# GS_01_Core.net
KiCad netlist of a schematic drawn in Altium Designer
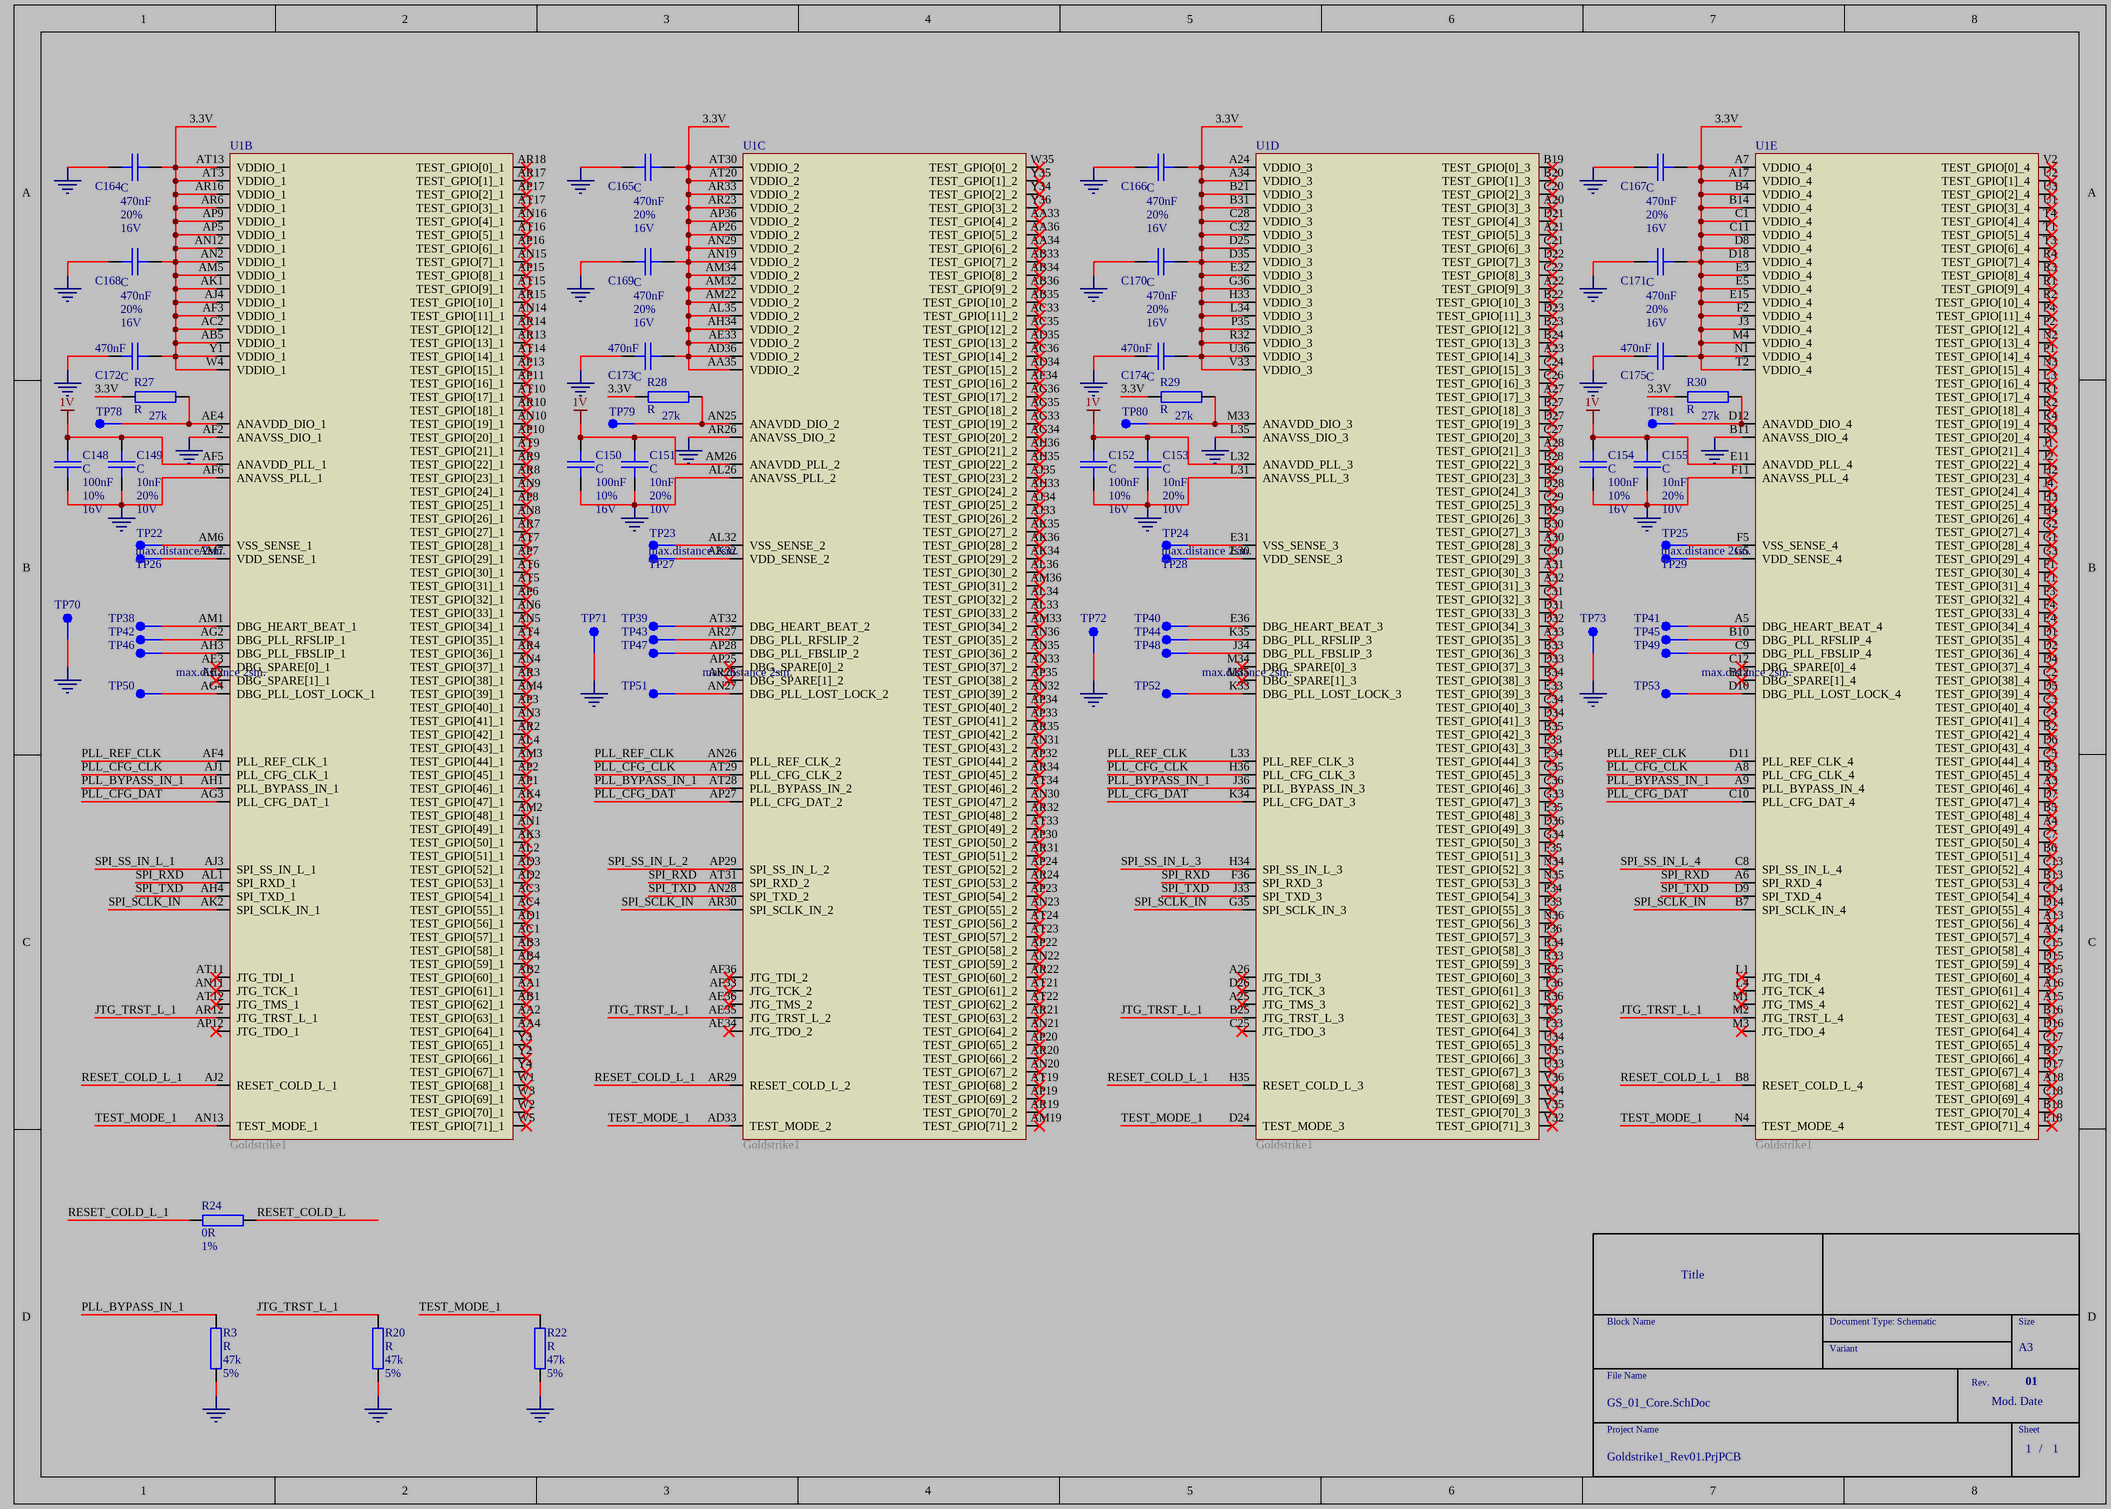
[diagram p0: GS_01_Core.SchDoc]

(export (version "E")
  (design (tool "Eeschema 10.0.6"))
  (components
    (comp (ref "C148")
      (value "C")
      (footprint "SMD_0603_CAPC1608X95N")
      (fields
        (field (name "DB_PART_NUMBER") "CAP000047357")
        (field (name "DB_VALUE") "100nF")
        (field (name "DB_TOLERANCE") "10%")
        (field (name "DB_VOLTAGE") "16V")
      )
      (libsource (lib "Database_Libs1") (part "C"))
    )
    (comp (ref "C149")
      (value "C")
      (footprint "SMD_0603_CAPC1608X95N")
      (fields
        (field (name "DB_PART_NUMBER") "CAP000038821")
        (field (name "DB_VALUE") "10nF")
        (field (name "DB_TOLERANCE") "20%")
        (field (name "DB_VOLTAGE") "10V")
      )
      (libsource (lib "Database_Libs1") (part "C"))
    )
    (comp (ref "C150")
      (value "C")
      (footprint "SMD_0603_CAPC1608X95N")
      (fields
        (field (name "DB_PART_NUMBER") "CAP000047357")
        (field (name "DB_VALUE") "100nF")
        (field (name "DB_TOLERANCE") "10%")
        (field (name "DB_VOLTAGE") "16V")
      )
      (libsource (lib "Database_Libs1") (part "C"))
    )
    (comp (ref "C151")
      (value "C")
      (footprint "SMD_0603_CAPC1608X95N")
      (fields
        (field (name "DB_PART_NUMBER") "CAP000038821")
        (field (name "DB_VALUE") "10nF")
        (field (name "DB_TOLERANCE") "20%")
        (field (name "DB_VOLTAGE") "10V")
      )
      (libsource (lib "Database_Libs1") (part "C"))
    )
    (comp (ref "C152")
      (value "C")
      (footprint "SMD_0603_CAPC1608X95N")
      (fields
        (field (name "DB_PART_NUMBER") "CAP000047357")
        (field (name "DB_VALUE") "100nF")
        (field (name "DB_TOLERANCE") "10%")
        (field (name "DB_VOLTAGE") "16V")
      )
      (libsource (lib "Database_Libs1") (part "C"))
    )
    (comp (ref "C153")
      (value "C")
      (footprint "SMD_0603_CAPC1608X95N")
      (fields
        (field (name "DB_PART_NUMBER") "CAP000038821")
        (field (name "DB_VALUE") "10nF")
        (field (name "DB_TOLERANCE") "20%")
        (field (name "DB_VOLTAGE") "10V")
      )
      (libsource (lib "Database_Libs1") (part "C"))
    )
    (comp (ref "C154")
      (value "C")
      (footprint "SMD_0603_CAPC1608X95N")
      (fields
        (field (name "DB_PART_NUMBER") "CAP000047357")
        (field (name "DB_VALUE") "100nF")
        (field (name "DB_TOLERANCE") "10%")
        (field (name "DB_VOLTAGE") "16V")
      )
      (libsource (lib "Database_Libs1") (part "C"))
    )
    (comp (ref "C155")
      (value "C")
      (footprint "SMD_0603_CAPC1608X95N")
      (fields
        (field (name "DB_PART_NUMBER") "CAP000038821")
        (field (name "DB_VALUE") "10nF")
        (field (name "DB_TOLERANCE") "20%")
        (field (name "DB_VOLTAGE") "10V")
      )
      (libsource (lib "Database_Libs1") (part "C"))
    )
    (comp (ref "C164")
      (value "C")
      (footprint "SMD_0603_CAPC1608X95N")
      (fields
        (field (name "DB_PART_NUMBER") "CAP000023179")
        (field (name "DB_VALUE") "470nF")
        (field (name "DB_TOLERANCE") "20%")
        (field (name "DB_VOLTAGE") "16V")
        (field (name "DB_MANUFACTURER_PART") "KEMET    C0603F474M4RAC")
      )
      (libsource (lib "Database_Libs1") (part "C"))
    )
    (comp (ref "C165")
      (value "C")
      (footprint "SMD_0603_CAPC1608X95N")
      (fields
        (field (name "DB_PART_NUMBER") "CAP000023179")
        (field (name "DB_VALUE") "470nF")
        (field (name "DB_TOLERANCE") "20%")
        (field (name "DB_VOLTAGE") "16V")
        (field (name "DB_MANUFACTURER_PART") "KEMET    C0603F474M4RAC")
      )
      (libsource (lib "Database_Libs1") (part "C"))
    )
    (comp (ref "C166")
      (value "C")
      (footprint "SMD_0603_CAPC1608X95N")
      (fields
        (field (name "DB_PART_NUMBER") "CAP000023179")
        (field (name "DB_VALUE") "470nF")
        (field (name "DB_TOLERANCE") "20%")
        (field (name "DB_VOLTAGE") "16V")
        (field (name "DB_MANUFACTURER_PART") "KEMET    C0603F474M4RAC")
      )
      (libsource (lib "Database_Libs1") (part "C"))
    )
    (comp (ref "C167")
      (value "C")
      (footprint "SMD_0603_CAPC1608X95N")
      (fields
        (field (name "DB_PART_NUMBER") "CAP000023179")
        (field (name "DB_VALUE") "470nF")
        (field (name "DB_TOLERANCE") "20%")
        (field (name "DB_VOLTAGE") "16V")
        (field (name "DB_MANUFACTURER_PART") "KEMET    C0603F474M4RAC")
      )
      (libsource (lib "Database_Libs1") (part "C"))
    )
    (comp (ref "C168")
      (value "C")
      (footprint "SMD_0603_CAPC1608X95N")
      (fields
        (field (name "DB_PART_NUMBER") "CAP000023179")
        (field (name "DB_VALUE") "470nF")
        (field (name "DB_TOLERANCE") "20%")
        (field (name "DB_VOLTAGE") "16V")
        (field (name "DB_MANUFACTURER_PART") "KEMET    C0603F474M4RAC")
      )
      (libsource (lib "Database_Libs1") (part "C"))
    )
    (comp (ref "C169")
      (value "C")
      (footprint "SMD_0603_CAPC1608X95N")
      (fields
        (field (name "DB_PART_NUMBER") "CAP000023179")
        (field (name "DB_VALUE") "470nF")
        (field (name "DB_TOLERANCE") "20%")
        (field (name "DB_VOLTAGE") "16V")
        (field (name "DB_MANUFACTURER_PART") "KEMET    C0603F474M4RAC")
      )
      (libsource (lib "Database_Libs1") (part "C"))
    )
    (comp (ref "C170")
      (value "C")
      (footprint "SMD_0603_CAPC1608X95N")
      (fields
        (field (name "DB_PART_NUMBER") "CAP000023179")
        (field (name "DB_VALUE") "470nF")
        (field (name "DB_TOLERANCE") "20%")
        (field (name "DB_VOLTAGE") "16V")
        (field (name "DB_MANUFACTURER_PART") "KEMET    C0603F474M4RAC")
      )
      (libsource (lib "Database_Libs1") (part "C"))
    )
    (comp (ref "C171")
      (value "C")
      (footprint "SMD_0603_CAPC1608X95N")
      (fields
        (field (name "DB_PART_NUMBER") "CAP000023179")
        (field (name "DB_VALUE") "470nF")
        (field (name "DB_TOLERANCE") "20%")
        (field (name "DB_VOLTAGE") "16V")
        (field (name "DB_MANUFACTURER_PART") "KEMET    C0603F474M4RAC")
      )
      (libsource (lib "Database_Libs1") (part "C"))
    )
    (comp (ref "C172")
      (value "C")
      (footprint "SMD_0603_CAPC1608X95N")
      (fields
        (field (name "DB_PART_NUMBER") "CAP000023179")
        (field (name "DB_VALUE") "470nF")
        (field (name "DB_MANUFACTURER_PART") "KEMET    C0603F474M4RAC")
      )
      (libsource (lib "Database_Libs1") (part "C"))
    )
    (comp (ref "C173")
      (value "C")
      (footprint "SMD_0603_CAPC1608X95N")
      (fields
        (field (name "DB_PART_NUMBER") "CAP000023179")
        (field (name "DB_VALUE") "470nF")
        (field (name "DB_MANUFACTURER_PART") "KEMET    C0603F474M4RAC")
      )
      (libsource (lib "Database_Libs1") (part "C"))
    )
    (comp (ref "C174")
      (value "C")
      (footprint "SMD_0603_CAPC1608X95N")
      (fields
        (field (name "DB_PART_NUMBER") "CAP000023179")
        (field (name "DB_VALUE") "470nF")
        (field (name "DB_MANUFACTURER_PART") "KEMET    C0603F474M4RAC")
      )
      (libsource (lib "Database_Libs1") (part "C"))
    )
    (comp (ref "C175")
      (value "C")
      (footprint "SMD_0603_CAPC1608X95N")
      (fields
        (field (name "DB_PART_NUMBER") "CAP000023179")
        (field (name "DB_VALUE") "470nF")
        (field (name "DB_MANUFACTURER_PART") "KEMET    C0603F474M4RAC")
      )
      (libsource (lib "Database_Libs1") (part "C"))
    )
    (comp (ref "R3")
      (value "R")
      (footprint "SMD_0603_RESC1608X55N")
      (fields
        (field (name "DB_PART_NUMBER") "RES000006462")
        (field (name "DB_VALUE") "47k")
        (field (name "DB_TOLERANCE") "5%")
        (field (name "DB_MANUFACTURER_PART") "YAGEO    RC0603JR-0747K")
      )
      (libsource (lib "Database_Libs1") (part "R"))
    )
    (comp (ref "R20")
      (value "R")
      (footprint "SMD_0603_RESC1608X55N")
      (fields
        (field (name "DB_PART_NUMBER") "RES000006462")
        (field (name "DB_VALUE") "47k")
        (field (name "DB_TOLERANCE") "5%")
        (field (name "DB_MANUFACTURER_PART") "YAGEO    RC0603JR-0747K")
      )
      (libsource (lib "Database_Libs1") (part "R"))
    )
    (comp (ref "R22")
      (value "R")
      (footprint "SMD_0603_RESC1608X55N")
      (fields
        (field (name "DB_PART_NUMBER") "RES000006462")
        (field (name "DB_VALUE") "47k")
        (field (name "DB_TOLERANCE") "5%")
        (field (name "DB_MANUFACTURER_PART") "YAGEO    RC0603JR-0747K")
      )
      (libsource (lib "Database_Libs1") (part "R"))
    )
    (comp (ref "R24")
      (value "R")
      (footprint "SMD_0603_RESC1608X55N")
      (fields
        (field (name "DB_PART_NUMBER") "RES000008926")
        (field (name "DB_VALUE") "0R")
        (field (name "DB_TOLERANCE") "1%")
        (field (name "DB_MANUFACTURER_PART") "YAGEO    AC0603FR-070RL")
        (field (name "DB_APPROVED_BY") "VSN")
      )
      (libsource (lib "Database_Libs1") (part "R"))
    )
    (comp (ref "R27")
      (value "R")
      (footprint "SMD_0603_RESC1608X55N")
      (fields
        (field (name "DB_PART_NUMBER") "RES000006456")
        (field (name "DB_VALUE") "27k")
        (field (name "DB_MANUFACTURER_PART") "YAGEO    RC0603JR-0727K")
      )
      (libsource (lib "Database_Libs1") (part "R"))
    )
    (comp (ref "R28")
      (value "R")
      (footprint "SMD_0603_RESC1608X55N")
      (fields
        (field (name "DB_PART_NUMBER") "RES000006456")
        (field (name "DB_VALUE") "27k")
        (field (name "DB_MANUFACTURER_PART") "YAGEO    RC0603JR-0727K")
      )
      (libsource (lib "Database_Libs1") (part "R"))
    )
    (comp (ref "R29")
      (value "R")
      (footprint "SMD_0603_RESC1608X55N")
      (fields
        (field (name "DB_PART_NUMBER") "RES000006456")
        (field (name "DB_VALUE") "27k")
        (field (name "DB_MANUFACTURER_PART") "YAGEO    RC0603JR-0727K")
      )
      (libsource (lib "Database_Libs1") (part "R"))
    )
    (comp (ref "R30")
      (value "R")
      (footprint "SMD_0603_RESC1608X55N")
      (fields
        (field (name "DB_PART_NUMBER") "RES000006456")
        (field (name "DB_VALUE") "27k")
        (field (name "DB_MANUFACTURER_PART") "YAGEO    RC0603JR-0727K")
      )
      (libsource (lib "Database_Libs1") (part "R"))
    )
    (comp (ref "TP22")
      (value "TEST_POINT_1")
      (footprint "SMD_TP_100-254")
      (fields (field (name "DB_PART_NUMBER") "TPO000000001"))
      (libsource (lib "Database_Libs1") (part "TEST_POINT_1"))
    )
    (comp (ref "TP23")
      (value "TEST_POINT_1")
      (footprint "SMD_TP_100-254")
      (fields (field (name "DB_PART_NUMBER") "TPO000000001"))
      (libsource (lib "Database_Libs1") (part "TEST_POINT_1"))
    )
    (comp (ref "TP24")
      (value "TEST_POINT_1")
      (footprint "SMD_TP_100-254")
      (fields (field (name "DB_PART_NUMBER") "TPO000000001"))
      (libsource (lib "Database_Libs1") (part "TEST_POINT_1"))
    )
    (comp (ref "TP25")
      (value "TEST_POINT_1")
      (footprint "SMD_TP_100-254")
      (fields (field (name "DB_PART_NUMBER") "TPO000000001"))
      (libsource (lib "Database_Libs1") (part "TEST_POINT_1"))
    )
    (comp (ref "TP26")
      (value "TEST_POINT_1")
      (footprint "SMD_TP_100-254")
      (fields (field (name "DB_PART_NUMBER") "TPO000000001"))
      (libsource (lib "Database_Libs1") (part "TEST_POINT_1"))
    )
    (comp (ref "TP27")
      (value "TEST_POINT_1")
      (footprint "SMD_TP_100-254")
      (fields (field (name "DB_PART_NUMBER") "TPO000000001"))
      (libsource (lib "Database_Libs1") (part "TEST_POINT_1"))
    )
    (comp (ref "TP28")
      (value "TEST_POINT_1")
      (footprint "SMD_TP_100-254")
      (fields (field (name "DB_PART_NUMBER") "TPO000000001"))
      (libsource (lib "Database_Libs1") (part "TEST_POINT_1"))
    )
    (comp (ref "TP29")
      (value "TEST_POINT_1")
      (footprint "SMD_TP_100-254")
      (fields (field (name "DB_PART_NUMBER") "TPO000000001"))
      (libsource (lib "Database_Libs1") (part "TEST_POINT_1"))
    )
    (comp (ref "TP38")
      (value "TEST_POINT_1")
      (footprint "SMD_TP_100-254")
      (fields (field (name "DB_PART_NUMBER") "TPO000000001"))
      (libsource (lib "Database_Libs1") (part "TEST_POINT_1"))
    )
    (comp (ref "TP39")
      (value "TEST_POINT_1")
      (footprint "SMD_TP_100-254")
      (fields (field (name "DB_PART_NUMBER") "TPO000000001"))
      (libsource (lib "Database_Libs1") (part "TEST_POINT_1"))
    )
    (comp (ref "TP40")
      (value "TEST_POINT_1")
      (footprint "SMD_TP_100-254")
      (fields (field (name "DB_PART_NUMBER") "TPO000000001"))
      (libsource (lib "Database_Libs1") (part "TEST_POINT_1"))
    )
    (comp (ref "TP41")
      (value "TEST_POINT_1")
      (footprint "SMD_TP_100-254")
      (fields (field (name "DB_PART_NUMBER") "TPO000000001"))
      (libsource (lib "Database_Libs1") (part "TEST_POINT_1"))
    )
    (comp (ref "TP42")
      (value "TEST_POINT_1")
      (footprint "SMD_TP_100-254")
      (fields (field (name "DB_PART_NUMBER") "TPO000000001"))
      (libsource (lib "Database_Libs1") (part "TEST_POINT_1"))
    )
    (comp (ref "TP43")
      (value "TEST_POINT_1")
      (footprint "SMD_TP_100-254")
      (fields (field (name "DB_PART_NUMBER") "TPO000000001"))
      (libsource (lib "Database_Libs1") (part "TEST_POINT_1"))
    )
    (comp (ref "TP44")
      (value "TEST_POINT_1")
      (footprint "SMD_TP_100-254")
      (fields (field (name "DB_PART_NUMBER") "TPO000000001"))
      (libsource (lib "Database_Libs1") (part "TEST_POINT_1"))
    )
    (comp (ref "TP45")
      (value "TEST_POINT_1")
      (footprint "SMD_TP_100-254")
      (fields (field (name "DB_PART_NUMBER") "TPO000000001"))
      (libsource (lib "Database_Libs1") (part "TEST_POINT_1"))
    )
    (comp (ref "TP46")
      (value "TEST_POINT_1")
      (footprint "SMD_TP_100-254")
      (fields (field (name "DB_PART_NUMBER") "TPO000000001"))
      (libsource (lib "Database_Libs1") (part "TEST_POINT_1"))
    )
    (comp (ref "TP47")
      (value "TEST_POINT_1")
      (footprint "SMD_TP_100-254")
      (fields (field (name "DB_PART_NUMBER") "TPO000000001"))
      (libsource (lib "Database_Libs1") (part "TEST_POINT_1"))
    )
    (comp (ref "TP48")
      (value "TEST_POINT_1")
      (footprint "SMD_TP_100-254")
      (fields (field (name "DB_PART_NUMBER") "TPO000000001"))
      (libsource (lib "Database_Libs1") (part "TEST_POINT_1"))
    )
    (comp (ref "TP49")
      (value "TEST_POINT_1")
      (footprint "SMD_TP_100-254")
      (fields (field (name "DB_PART_NUMBER") "TPO000000001"))
      (libsource (lib "Database_Libs1") (part "TEST_POINT_1"))
    )
    (comp (ref "TP50")
      (value "TEST_POINT_1")
      (footprint "SMD_TP_100-254")
      (fields (field (name "DB_PART_NUMBER") "TPO000000001"))
      (libsource (lib "Database_Libs1") (part "TEST_POINT_1"))
    )
    (comp (ref "TP51")
      (value "TEST_POINT_1")
      (footprint "SMD_TP_100-254")
      (fields (field (name "DB_PART_NUMBER") "TPO000000001"))
      (libsource (lib "Database_Libs1") (part "TEST_POINT_1"))
    )
    (comp (ref "TP52")
      (value "TEST_POINT_1")
      (footprint "SMD_TP_100-254")
      (fields (field (name "DB_PART_NUMBER") "TPO000000001"))
      (libsource (lib "Database_Libs1") (part "TEST_POINT_1"))
    )
    (comp (ref "TP53")
      (value "TEST_POINT_1")
      (footprint "SMD_TP_100-254")
      (fields (field (name "DB_PART_NUMBER") "TPO000000001"))
      (libsource (lib "Database_Libs1") (part "TEST_POINT_1"))
    )
    (comp (ref "TP70")
      (value "TEST_POINT_1")
      (footprint "SMD_TP_100-254")
      (fields (field (name "DB_PART_NUMBER") "TPO000000001"))
      (libsource (lib "Database_Libs1") (part "TEST_POINT_1"))
    )
    (comp (ref "TP71")
      (value "TEST_POINT_1")
      (footprint "SMD_TP_100-254")
      (fields (field (name "DB_PART_NUMBER") "TPO000000001"))
      (libsource (lib "Database_Libs1") (part "TEST_POINT_1"))
    )
    (comp (ref "TP72")
      (value "TEST_POINT_1")
      (footprint "SMD_TP_100-254")
      (fields (field (name "DB_PART_NUMBER") "TPO000000001"))
      (libsource (lib "Database_Libs1") (part "TEST_POINT_1"))
    )
    (comp (ref "TP73")
      (value "TEST_POINT_1")
      (footprint "SMD_TP_100-254")
      (fields (field (name "DB_PART_NUMBER") "TPO000000001"))
      (libsource (lib "Database_Libs1") (part "TEST_POINT_1"))
    )
    (comp (ref "TP78")
      (value "TEST_POINT_1")
      (footprint "SMD_TP_100-254")
      (fields (field (name "DB_PART_NUMBER") "TPO000000001"))
      (libsource (lib "Database_Libs1") (part "TEST_POINT_1"))
    )
    (comp (ref "TP79")
      (value "TEST_POINT_1")
      (footprint "SMD_TP_100-254")
      (fields (field (name "DB_PART_NUMBER") "TPO000000001"))
      (libsource (lib "Database_Libs1") (part "TEST_POINT_1"))
    )
    (comp (ref "TP80")
      (value "TEST_POINT_1")
      (footprint "SMD_TP_100-254")
      (fields (field (name "DB_PART_NUMBER") "TPO000000001"))
      (libsource (lib "Database_Libs1") (part "TEST_POINT_1"))
    )
    (comp (ref "TP81")
      (value "TEST_POINT_1")
      (footprint "SMD_TP_100-254")
      (fields (field (name "DB_PART_NUMBER") "TPO000000001"))
      (libsource (lib "Database_Libs1") (part "TEST_POINT_1"))
    )
    (comp (ref "U1") (value "Goldstrike1") (libsource (lib "Schlib1") (part "Goldstrike1")))
  )
  (nets
    (net (code "1") (name "/3.3V") (class "Default")
      (node (ref "C164") (pin "2") (pinfunction "2_2") (pintype "passive"))
      (node (ref "C165") (pin "2") (pinfunction "2_2") (pintype "passive"))
      (node (ref "C166") (pin "2") (pinfunction "2_2") (pintype "passive"))
      (node (ref "C167") (pin "2") (pinfunction "2_2") (pintype "passive"))
      (node (ref "C168") (pin "2") (pinfunction "2_2") (pintype "passive"))
      (node (ref "C169") (pin "2") (pinfunction "2_2") (pintype "passive"))
      (node (ref "C170") (pin "2") (pinfunction "2_2") (pintype "passive"))
      (node (ref "C171") (pin "2") (pinfunction "2_2") (pintype "passive"))
      (node (ref "C172") (pin "2") (pinfunction "2_2") (pintype "passive"))
      (node (ref "C173") (pin "2") (pinfunction "2_2") (pintype "passive"))
      (node (ref "C174") (pin "2") (pinfunction "2_2") (pintype "passive"))
      (node (ref "C175") (pin "2") (pinfunction "2_2") (pintype "passive"))
      (node (ref "R27") (pin "1") (pinfunction "1_1") (pintype "passive"))
      (node (ref "R28") (pin "1") (pinfunction "1_1") (pintype "passive"))
      (node (ref "R29") (pin "1") (pinfunction "1_1") (pintype "passive"))
      (node (ref "R30") (pin "1") (pinfunction "1_1") (pintype "passive"))
      (node (ref "U1") (pin "A17") (pinfunction "VDDIO_4_A17") (pintype "passive"))
      (node (ref "U1") (pin "A24") (pinfunction "VDDIO_3_A24") (pintype "passive"))
      (node (ref "U1") (pin "A34") (pinfunction "VDDIO_3_A34") (pintype "passive"))
      (node (ref "U1") (pin "A7") (pinfunction "VDDIO_4_A7") (pintype "passive"))
      (node (ref "U1") (pin "AA35") (pinfunction "VDDIO_2_AA35") (pintype "passive"))
      (node (ref "U1") (pin "AB5") (pinfunction "VDDIO_1_AB5") (pintype "passive"))
      (node (ref "U1") (pin "AC2") (pinfunction "VDDIO_1_AC2") (pintype "passive"))
      (node (ref "U1") (pin "AD36") (pinfunction "VDDIO_2_AD36") (pintype "passive"))
      (node (ref "U1") (pin "AE33") (pinfunction "VDDIO_2_AE33") (pintype "passive"))
      (node (ref "U1") (pin "AF3") (pinfunction "VDDIO_1_AF3") (pintype "passive"))
      (node (ref "U1") (pin "AH34") (pinfunction "VDDIO_2_AH34") (pintype "passive"))
      (node (ref "U1") (pin "AJ4") (pinfunction "VDDIO_1_AJ4") (pintype "passive"))
      (node (ref "U1") (pin "AK1") (pinfunction "VDDIO_1_AK1") (pintype "passive"))
      (node (ref "U1") (pin "AL35") (pinfunction "VDDIO_2_AL35") (pintype "passive"))
      (node (ref "U1") (pin "AM22") (pinfunction "VDDIO_2_AM22") (pintype "passive"))
      (node (ref "U1") (pin "AM32") (pinfunction "VDDIO_2_AM32") (pintype "passive"))
      (node (ref "U1") (pin "AM34") (pinfunction "VDDIO_2_AM34") (pintype "passive"))
      (node (ref "U1") (pin "AM5") (pinfunction "VDDIO_1_AM5") (pintype "passive"))
      (node (ref "U1") (pin "AN12") (pinfunction "VDDIO_1_AN12") (pintype "passive"))
      (node (ref "U1") (pin "AN19") (pinfunction "VDDIO_2_AN19") (pintype "passive"))
      (node (ref "U1") (pin "AN2") (pinfunction "VDDIO_1_AN2") (pintype "passive"))
      (node (ref "U1") (pin "AN29") (pinfunction "VDDIO_2_AN29") (pintype "passive"))
      (node (ref "U1") (pin "AP26") (pinfunction "VDDIO_2_AP26") (pintype "passive"))
      (node (ref "U1") (pin "AP36") (pinfunction "VDDIO_2_AP36") (pintype "passive"))
      (node (ref "U1") (pin "AP5") (pinfunction "VDDIO_1_AP5") (pintype "passive"))
      (node (ref "U1") (pin "AP9") (pinfunction "VDDIO_1_AP9") (pintype "passive"))
      (node (ref "U1") (pin "AR16") (pinfunction "VDDIO_1_AR16") (pintype "passive"))
      (node (ref "U1") (pin "AR23") (pinfunction "VDDIO_2_AR23") (pintype "passive"))
      (node (ref "U1") (pin "AR33") (pinfunction "VDDIO_2_AR33") (pintype "passive"))
      (node (ref "U1") (pin "AR6") (pinfunction "VDDIO_1_AR6") (pintype "passive"))
      (node (ref "U1") (pin "AT13") (pinfunction "VDDIO_1_AT13") (pintype "passive"))
      (node (ref "U1") (pin "AT20") (pinfunction "VDDIO_2_AT20") (pintype "passive"))
      (node (ref "U1") (pin "AT3") (pinfunction "VDDIO_1_AT3") (pintype "passive"))
      (node (ref "U1") (pin "AT30") (pinfunction "VDDIO_2_AT30") (pintype "passive"))
      (node (ref "U1") (pin "B14") (pinfunction "VDDIO_4_B14") (pintype "passive"))
      (node (ref "U1") (pin "B21") (pinfunction "VDDIO_3_B21") (pintype "passive"))
      (node (ref "U1") (pin "B31") (pinfunction "VDDIO_3_B31") (pintype "passive"))
      (node (ref "U1") (pin "B4") (pinfunction "VDDIO_4_B4") (pintype "passive"))
      (node (ref "U1") (pin "C1") (pinfunction "VDDIO_4_C1") (pintype "passive"))
      (node (ref "U1") (pin "C11") (pinfunction "VDDIO_4_C11") (pintype "passive"))
      (node (ref "U1") (pin "C28") (pinfunction "VDDIO_3_C28") (pintype "passive"))
      (node (ref "U1") (pin "C32") (pinfunction "VDDIO_3_C32") (pintype "passive"))
      (node (ref "U1") (pin "D18") (pinfunction "VDDIO_4_D18") (pintype "passive"))
      (node (ref "U1") (pin "D25") (pinfunction "VDDIO_3_D25") (pintype "passive"))
      (node (ref "U1") (pin "D35") (pinfunction "VDDIO_3_D35") (pintype "passive"))
      (node (ref "U1") (pin "D8") (pinfunction "VDDIO_4_D8") (pintype "passive"))
      (node (ref "U1") (pin "E15") (pinfunction "VDDIO_4_E15") (pintype "passive"))
      (node (ref "U1") (pin "E3") (pinfunction "VDDIO_4_E3") (pintype "passive"))
      (node (ref "U1") (pin "E32") (pinfunction "VDDIO_3_E32") (pintype "passive"))
      (node (ref "U1") (pin "E5") (pinfunction "VDDIO_4_E5") (pintype "passive"))
      (node (ref "U1") (pin "F2") (pinfunction "VDDIO_4_F2") (pintype "passive"))
      (node (ref "U1") (pin "G36") (pinfunction "VDDIO_3_G36") (pintype "passive"))
      (node (ref "U1") (pin "H33") (pinfunction "VDDIO_3_H33") (pintype "passive"))
      (node (ref "U1") (pin "J3") (pinfunction "VDDIO_4_J3") (pintype "passive"))
      (node (ref "U1") (pin "L34") (pinfunction "VDDIO_3_L34") (pintype "passive"))
      (node (ref "U1") (pin "M4") (pinfunction "VDDIO_4_M4") (pintype "passive"))
      (node (ref "U1") (pin "N1") (pinfunction "VDDIO_4_N1") (pintype "passive"))
      (node (ref "U1") (pin "P35") (pinfunction "VDDIO_3_P35") (pintype "passive"))
      (node (ref "U1") (pin "R32") (pinfunction "VDDIO_3_R32") (pintype "passive"))
      (node (ref "U1") (pin "T2") (pinfunction "VDDIO_4_T2") (pintype "passive"))
      (node (ref "U1") (pin "U36") (pinfunction "VDDIO_3_U36") (pintype "passive"))
      (node (ref "U1") (pin "V33") (pinfunction "VDDIO_3_V33") (pintype "passive"))
      (node (ref "U1") (pin "W4") (pinfunction "VDDIO_1_W4") (pintype "passive"))
      (node (ref "U1") (pin "Y1") (pinfunction "VDDIO_1_Y1") (pintype "passive"))
    )
    (net (code "2") (name "/JTG_TRST_L_1") (class "Default")
      (node (ref "R20") (pin "1") (pinfunction "1_1") (pintype "passive"))
      (node (ref "U1") (pin "AE35") (pinfunction "JTG_TRST_L_2_AE35") (pintype "passive"))
      (node (ref "U1") (pin "AR12") (pinfunction "JTG_TRST_L_1_AR12") (pintype "passive"))
      (node (ref "U1") (pin "B25") (pinfunction "JTG_TRST_L_3_B25") (pintype "passive"))
      (node (ref "U1") (pin "M2") (pinfunction "JTG_TRST_L_4_M2") (pintype "passive"))
    )
    (net (code "3") (name "/PLL_BYPASS_IN_1") (class "Default")
      (node (ref "R3") (pin "1") (pinfunction "1_1") (pintype "passive"))
      (node (ref "U1") (pin "A9") (pinfunction "PLL_BYPASS_IN_4_A9") (pintype "passive"))
      (node (ref "U1") (pin "AH1") (pinfunction "PLL_BYPASS_IN_1_AH1") (pintype "passive"))
      (node (ref "U1") (pin "AT28") (pinfunction "PLL_BYPASS_IN_2_AT28") (pintype "passive"))
      (node (ref "U1") (pin "J36") (pinfunction "PLL_BYPASS_IN_3_J36") (pintype "passive"))
    )
    (net (code "4") (name "/PLL_CFG_CLK") (class "Default")
      (node (ref "U1") (pin "A8") (pinfunction "PLL_CFG_CLK_4_A8") (pintype "passive"))
      (node (ref "U1") (pin "AJ1") (pinfunction "PLL_CFG_CLK_1_AJ1") (pintype "passive"))
      (node (ref "U1") (pin "AT29") (pinfunction "PLL_CFG_CLK_2_AT29") (pintype "passive"))
      (node (ref "U1") (pin "H36") (pinfunction "PLL_CFG_CLK_3_H36") (pintype "passive"))
    )
    (net (code "5") (name "/PLL_CFG_DAT") (class "Default")
      (node (ref "U1") (pin "AG3") (pinfunction "PLL_CFG_DAT_1_AG3") (pintype "passive"))
      (node (ref "U1") (pin "AP27") (pinfunction "PLL_CFG_DAT_2_AP27") (pintype "passive"))
      (node (ref "U1") (pin "C10") (pinfunction "PLL_CFG_DAT_4_C10") (pintype "passive"))
      (node (ref "U1") (pin "K34") (pinfunction "PLL_CFG_DAT_3_K34") (pintype "passive"))
    )
    (net (code "6") (name "/PLL_REF_CLK") (class "Default")
      (node (ref "U1") (pin "AF4") (pinfunction "PLL_REF_CLK_1_AF4") (pintype "passive"))
      (node (ref "U1") (pin "AN26") (pinfunction "PLL_REF_CLK_2_AN26") (pintype "passive"))
      (node (ref "U1") (pin "D11") (pinfunction "PLL_REF_CLK_4_D11") (pintype "passive"))
      (node (ref "U1") (pin "L33") (pinfunction "PLL_REF_CLK_3_L33") (pintype "passive"))
    )
    (net (code "7") (name "/RESET_COLD_L") (class "Default")
      (node (ref "R24") (pin "1") (pinfunction "1_1") (pintype "passive"))
    )
    (net (code "8") (name "/RESET_COLD_L_1") (class "Default")
      (node (ref "R24") (pin "2") (pinfunction "2_2") (pintype "passive"))
      (node (ref "U1") (pin "AJ2") (pinfunction "RESET_COLD_L_1_AJ2") (pintype "passive"))
      (node (ref "U1") (pin "AR29") (pinfunction "RESET_COLD_L_2_AR29") (pintype "passive"))
      (node (ref "U1") (pin "B8") (pinfunction "RESET_COLD_L_4_B8") (pintype "passive"))
      (node (ref "U1") (pin "H35") (pinfunction "RESET_COLD_L_3_H35") (pintype "passive"))
    )
    (net (code "9") (name "/SPI_RXD") (class "Default")
      (node (ref "U1") (pin "A6") (pinfunction "SPI_RXD_4_A6") (pintype "passive"))
      (node (ref "U1") (pin "AL1") (pinfunction "SPI_RXD_1_AL1") (pintype "passive"))
      (node (ref "U1") (pin "AT31") (pinfunction "SPI_RXD_2_AT31") (pintype "passive"))
      (node (ref "U1") (pin "F36") (pinfunction "SPI_RXD_3_F36") (pintype "passive"))
    )
    (net (code "10") (name "/SPI_SCLK_IN") (class "Default")
      (node (ref "U1") (pin "AK2") (pinfunction "SPI_SCLK_IN_1_AK2") (pintype "passive"))
      (node (ref "U1") (pin "AR30") (pinfunction "SPI_SCLK_IN_2_AR30") (pintype "passive"))
      (node (ref "U1") (pin "B7") (pinfunction "SPI_SCLK_IN_4_B7") (pintype "passive"))
      (node (ref "U1") (pin "G35") (pinfunction "SPI_SCLK_IN_3_G35") (pintype "passive"))
    )
    (net (code "11") (name "/SPI_SS_IN_L_1") (class "Default")
      (node (ref "U1") (pin "AJ3") (pinfunction "SPI_SS_IN_L_1_AJ3") (pintype "passive"))
    )
    (net (code "12") (name "/SPI_SS_IN_L_2") (class "Default")
      (node (ref "U1") (pin "AP29") (pinfunction "SPI_SS_IN_L_2_AP29") (pintype "passive"))
    )
    (net (code "13") (name "/SPI_SS_IN_L_3") (class "Default")
      (node (ref "U1") (pin "H34") (pinfunction "SPI_SS_IN_L_3_H34") (pintype "passive"))
    )
    (net (code "14") (name "/SPI_SS_IN_L_4") (class "Default")
      (node (ref "U1") (pin "C8") (pinfunction "SPI_SS_IN_L_4_C8") (pintype "passive"))
    )
    (net (code "15") (name "/SPI_TXD") (class "Default")
      (node (ref "U1") (pin "AH4") (pinfunction "SPI_TXD_1_AH4") (pintype "passive"))
      (node (ref "U1") (pin "AN28") (pinfunction "SPI_TXD_2_AN28") (pintype "passive"))
      (node (ref "U1") (pin "D9") (pinfunction "SPI_TXD_4_D9") (pintype "passive"))
      (node (ref "U1") (pin "J33") (pinfunction "SPI_TXD_3_J33") (pintype "passive"))
    )
    (net (code "16") (name "/TEST_MODE_1") (class "Default")
      (node (ref "R22") (pin "1") (pinfunction "1_1") (pintype "passive"))
      (node (ref "U1") (pin "AD33") (pinfunction "TEST_MODE_2_AD33") (pintype "passive"))
      (node (ref "U1") (pin "AN13") (pinfunction "TEST_MODE_1_AN13") (pintype "passive"))
      (node (ref "U1") (pin "D24") (pinfunction "TEST_MODE_3_D24") (pintype "passive"))
      (node (ref "U1") (pin "N4") (pinfunction "TEST_MODE_4_N4") (pintype "passive"))
    )
    (net (code "17") (name "1V") (class "Default")
      (node (ref "C148") (pin "1") (pinfunction "1_1") (pintype "passive"))
      (node (ref "C149") (pin "1") (pinfunction "1_1") (pintype "passive"))
      (node (ref "C150") (pin "1") (pinfunction "1_1") (pintype "passive"))
      (node (ref "C151") (pin "1") (pinfunction "1_1") (pintype "passive"))
      (node (ref "C152") (pin "1") (pinfunction "1_1") (pintype "passive"))
      (node (ref "C153") (pin "1") (pinfunction "1_1") (pintype "passive"))
      (node (ref "C154") (pin "1") (pinfunction "1_1") (pintype "passive"))
      (node (ref "C155") (pin "1") (pinfunction "1_1") (pintype "passive"))
      (node (ref "U1") (pin "AF5") (pinfunction "ANAVDD_PLL_1_AF5") (pintype "passive"))
      (node (ref "U1") (pin "AM26") (pinfunction "ANAVDD_PLL_2_AM26") (pintype "passive"))
      (node (ref "U1") (pin "E11") (pinfunction "ANAVDD_PLL_4_E11") (pintype "passive"))
      (node (ref "U1") (pin "L32") (pinfunction "ANAVDD_PLL_3_L32") (pintype "passive"))
    )
    (net (code "18") (name "GND") (class "Default")
      (node (ref "C148") (pin "2") (pinfunction "2_2") (pintype "passive"))
      (node (ref "C149") (pin "2") (pinfunction "2_2") (pintype "passive"))
      (node (ref "C150") (pin "2") (pinfunction "2_2") (pintype "passive"))
      (node (ref "C151") (pin "2") (pinfunction "2_2") (pintype "passive"))
      (node (ref "C152") (pin "2") (pinfunction "2_2") (pintype "passive"))
      (node (ref "C153") (pin "2") (pinfunction "2_2") (pintype "passive"))
      (node (ref "C154") (pin "2") (pinfunction "2_2") (pintype "passive"))
      (node (ref "C155") (pin "2") (pinfunction "2_2") (pintype "passive"))
      (node (ref "C164") (pin "1") (pinfunction "1_1") (pintype "passive"))
      (node (ref "C165") (pin "1") (pinfunction "1_1") (pintype "passive"))
      (node (ref "C166") (pin "1") (pinfunction "1_1") (pintype "passive"))
      (node (ref "C167") (pin "1") (pinfunction "1_1") (pintype "passive"))
      (node (ref "C168") (pin "1") (pinfunction "1_1") (pintype "passive"))
      (node (ref "C169") (pin "1") (pinfunction "1_1") (pintype "passive"))
      (node (ref "C170") (pin "1") (pinfunction "1_1") (pintype "passive"))
      (node (ref "C171") (pin "1") (pinfunction "1_1") (pintype "passive"))
      (node (ref "C172") (pin "1") (pinfunction "1_1") (pintype "passive"))
      (node (ref "C173") (pin "1") (pinfunction "1_1") (pintype "passive"))
      (node (ref "C174") (pin "1") (pinfunction "1_1") (pintype "passive"))
      (node (ref "C175") (pin "1") (pinfunction "1_1") (pintype "passive"))
      (node (ref "R20") (pin "2") (pinfunction "2_2") (pintype "passive"))
      (node (ref "R22") (pin "2") (pinfunction "2_2") (pintype "passive"))
      (node (ref "R3") (pin "2") (pinfunction "2_2") (pintype "passive"))
      (node (ref "TP70") (pin "1") (pinfunction "1_1") (pintype "passive"))
      (node (ref "TP71") (pin "1") (pinfunction "1_1") (pintype "passive"))
      (node (ref "TP72") (pin "1") (pinfunction "1_1") (pintype "passive"))
      (node (ref "TP73") (pin "1") (pinfunction "1_1") (pintype "passive"))
      (node (ref "U1") (pin "AF2") (pinfunction "ANAVSS_DIO_1_AF2") (pintype "passive"))
      (node (ref "U1") (pin "AF6") (pinfunction "ANAVSS_PLL_1_AF6") (pintype "passive"))
      (node (ref "U1") (pin "AL26") (pinfunction "ANAVSS_PLL_2_AL26") (pintype "passive"))
      (node (ref "U1") (pin "AR26") (pinfunction "ANAVSS_DIO_2_AR26") (pintype "passive"))
      (node (ref "U1") (pin "B11") (pinfunction "ANAVSS_DIO_4_B11") (pintype "passive"))
      (node (ref "U1") (pin "F11") (pinfunction "ANAVSS_PLL_4_F11") (pintype "passive"))
      (node (ref "U1") (pin "L31") (pinfunction "ANAVSS_PLL_3_L31") (pintype "passive"))
      (node (ref "U1") (pin "L35") (pinfunction "ANAVSS_DIO_3_L35") (pintype "passive"))
    )
    (net (code "19") (name "Net-(U1B-ANAVDD_DIO_1)") (class "Default")
      (node (ref "R27") (pin "2") (pinfunction "2_2") (pintype "passive"))
      (node (ref "TP78") (pin "1") (pinfunction "1_1") (pintype "passive"))
      (node (ref "U1") (pin "AE4") (pinfunction "ANAVDD_DIO_1_AE4") (pintype "passive"))
    )
    (net (code "20") (name "Net-(U1B-DBG_HEART_BEAT_1)") (class "Default")
      (node (ref "TP38") (pin "1") (pinfunction "1_1") (pintype "passive"))
      (node (ref "U1") (pin "AM1") (pinfunction "DBG_HEART_BEAT_1_AM1") (pintype "passive"))
    )
    (net (code "21") (name "Net-(U1B-DBG_PLL_FBSLIP_1)") (class "Default")
      (node (ref "TP46") (pin "1") (pinfunction "1_1") (pintype "passive"))
      (node (ref "U1") (pin "AH3") (pinfunction "DBG_PLL_FBSLIP_1_AH3") (pintype "passive"))
    )
    (net (code "22") (name "Net-(U1B-DBG_PLL_LOST_LOCK_1)") (class "Default")
      (node (ref "TP50") (pin "1") (pinfunction "1_1") (pintype "passive"))
      (node (ref "U1") (pin "AG4") (pinfunction "DBG_PLL_LOST_LOCK_1_AG4") (pintype "passive"))
    )
    (net (code "23") (name "Net-(U1B-DBG_PLL_RFSLIP_1)") (class "Default")
      (node (ref "TP42") (pin "1") (pinfunction "1_1") (pintype "passive"))
      (node (ref "U1") (pin "AG2") (pinfunction "DBG_PLL_RFSLIP_1_AG2") (pintype "passive"))
    )
    (net (code "24") (name "Net-(U1B-VDD_SENSE_1)") (class "Default")
      (node (ref "TP26") (pin "1") (pinfunction "1_1") (pintype "passive"))
      (node (ref "U1") (pin "AM7") (pinfunction "VDD_SENSE_1_AM7") (pintype "passive"))
    )
    (net (code "25") (name "Net-(U1B-VSS_SENSE_1)") (class "Default")
      (node (ref "TP22") (pin "1") (pinfunction "1_1") (pintype "passive"))
      (node (ref "U1") (pin "AM6") (pinfunction "VSS_SENSE_1_AM6") (pintype "passive"))
    )
    (net (code "26") (name "Net-(U1C-ANAVDD_DIO_2)") (class "Default")
      (node (ref "R28") (pin "2") (pinfunction "2_2") (pintype "passive"))
      (node (ref "TP79") (pin "1") (pinfunction "1_1") (pintype "passive"))
      (node (ref "U1") (pin "AN25") (pinfunction "ANAVDD_DIO_2_AN25") (pintype "passive"))
    )
    (net (code "27") (name "Net-(U1C-DBG_HEART_BEAT_2)") (class "Default")
      (node (ref "TP39") (pin "1") (pinfunction "1_1") (pintype "passive"))
      (node (ref "U1") (pin "AT32") (pinfunction "DBG_HEART_BEAT_2_AT32") (pintype "passive"))
    )
    (net (code "28") (name "Net-(U1C-DBG_PLL_FBSLIP_2)") (class "Default")
      (node (ref "TP47") (pin "1") (pinfunction "1_1") (pintype "passive"))
      (node (ref "U1") (pin "AP28") (pinfunction "DBG_PLL_FBSLIP_2_AP28") (pintype "passive"))
    )
    (net (code "29") (name "Net-(U1C-DBG_PLL_LOST_LOCK_2)") (class "Default")
      (node (ref "TP51") (pin "1") (pinfunction "1_1") (pintype "passive"))
      (node (ref "U1") (pin "AN27") (pinfunction "DBG_PLL_LOST_LOCK_2_AN27") (pintype "passive"))
    )
    (net (code "30") (name "Net-(U1C-DBG_PLL_RFSLIP_2)") (class "Default")
      (node (ref "TP43") (pin "1") (pinfunction "1_1") (pintype "passive"))
      (node (ref "U1") (pin "AR27") (pinfunction "DBG_PLL_RFSLIP_2_AR27") (pintype "passive"))
    )
    (net (code "31") (name "Net-(U1C-VDD_SENSE_2)") (class "Default")
      (node (ref "TP27") (pin "1") (pinfunction "1_1") (pintype "passive"))
      (node (ref "U1") (pin "AK32") (pinfunction "VDD_SENSE_2_AK32") (pintype "passive"))
    )
    (net (code "32") (name "Net-(U1C-VSS_SENSE_2)") (class "Default")
      (node (ref "TP23") (pin "1") (pinfunction "1_1") (pintype "passive"))
      (node (ref "U1") (pin "AL32") (pinfunction "VSS_SENSE_2_AL32") (pintype "passive"))
    )
    (net (code "33") (name "Net-(U1D-ANAVDD_DIO_3)") (class "Default")
      (node (ref "R29") (pin "2") (pinfunction "2_2") (pintype "passive"))
      (node (ref "TP80") (pin "1") (pinfunction "1_1") (pintype "passive"))
      (node (ref "U1") (pin "M33") (pinfunction "ANAVDD_DIO_3_M33") (pintype "passive"))
    )
    (net (code "34") (name "Net-(U1D-DBG_HEART_BEAT_3)") (class "Default")
      (node (ref "TP40") (pin "1") (pinfunction "1_1") (pintype "passive"))
      (node (ref "U1") (pin "E36") (pinfunction "DBG_HEART_BEAT_3_E36") (pintype "passive"))
    )
    (net (code "35") (name "Net-(U1D-DBG_PLL_FBSLIP_3)") (class "Default")
      (node (ref "TP48") (pin "1") (pinfunction "1_1") (pintype "passive"))
      (node (ref "U1") (pin "J34") (pinfunction "DBG_PLL_FBSLIP_3_J34") (pintype "passive"))
    )
    (net (code "36") (name "Net-(U1D-DBG_PLL_LOST_LOCK_3)") (class "Default")
      (node (ref "TP52") (pin "1") (pinfunction "1_1") (pintype "passive"))
      (node (ref "U1") (pin "K33") (pinfunction "DBG_PLL_LOST_LOCK_3_K33") (pintype "passive"))
    )
    (net (code "37") (name "Net-(U1D-DBG_PLL_RFSLIP_3)") (class "Default")
      (node (ref "TP44") (pin "1") (pinfunction "1_1") (pintype "passive"))
      (node (ref "U1") (pin "K35") (pinfunction "DBG_PLL_RFSLIP_3_K35") (pintype "passive"))
    )
    (net (code "38") (name "Net-(U1D-VDD_SENSE_3)") (class "Default")
      (node (ref "TP28") (pin "1") (pinfunction "1_1") (pintype "passive"))
      (node (ref "U1") (pin "E30") (pinfunction "VDD_SENSE_3_E30") (pintype "passive"))
    )
    (net (code "39") (name "Net-(U1D-VSS_SENSE_3)") (class "Default")
      (node (ref "TP24") (pin "1") (pinfunction "1_1") (pintype "passive"))
      (node (ref "U1") (pin "E31") (pinfunction "VSS_SENSE_3_E31") (pintype "passive"))
    )
    (net (code "40") (name "Net-(U1E-ANAVDD_DIO_4)") (class "Default")
      (node (ref "R30") (pin "2") (pinfunction "2_2") (pintype "passive"))
      (node (ref "TP81") (pin "1") (pinfunction "1_1") (pintype "passive"))
      (node (ref "U1") (pin "D12") (pinfunction "ANAVDD_DIO_4_D12") (pintype "passive"))
    )
    (net (code "41") (name "Net-(U1E-DBG_HEART_BEAT_4)") (class "Default")
      (node (ref "TP41") (pin "1") (pinfunction "1_1") (pintype "passive"))
      (node (ref "U1") (pin "A5") (pinfunction "DBG_HEART_BEAT_4_A5") (pintype "passive"))
    )
    (net (code "42") (name "Net-(U1E-DBG_PLL_FBSLIP_4)") (class "Default")
      (node (ref "TP49") (pin "1") (pinfunction "1_1") (pintype "passive"))
      (node (ref "U1") (pin "C9") (pinfunction "DBG_PLL_FBSLIP_4_C9") (pintype "passive"))
    )
    (net (code "43") (name "Net-(U1E-DBG_PLL_LOST_LOCK_4)") (class "Default")
      (node (ref "TP53") (pin "1") (pinfunction "1_1") (pintype "passive"))
      (node (ref "U1") (pin "D10") (pinfunction "DBG_PLL_LOST_LOCK_4_D10") (pintype "passive"))
    )
    (net (code "44") (name "Net-(U1E-DBG_PLL_RFSLIP_4)") (class "Default")
      (node (ref "TP45") (pin "1") (pinfunction "1_1") (pintype "passive"))
      (node (ref "U1") (pin "B10") (pinfunction "DBG_PLL_RFSLIP_4_B10") (pintype "passive"))
    )
    (net (code "45") (name "Net-(U1E-VDD_SENSE_4)") (class "Default")
      (node (ref "TP29") (pin "1") (pinfunction "1_1") (pintype "passive"))
      (node (ref "U1") (pin "G5") (pinfunction "VDD_SENSE_4_G5") (pintype "passive"))
    )
    (net (code "46") (name "Net-(U1E-VSS_SENSE_4)") (class "Default")
      (node (ref "TP25") (pin "1") (pinfunction "1_1") (pintype "passive"))
      (node (ref "U1") (pin "F5") (pinfunction "VSS_SENSE_4_F5") (pintype "passive"))
    )
    (net (code "47") (name "unconnected-(U1B-DBG_SPARE[0]_1-PadAE3)") (class "Default")
      (node (ref "U1") (pin "AE3") (pinfunction "DBG_SPARE[0]_1_AE3") (pintype "passive+no_connect"))
    )
    (net (code "48") (name "unconnected-(U1B-DBG_SPARE[1]_1-PadAE2)") (class "Default")
      (node (ref "U1") (pin "AE2") (pinfunction "DBG_SPARE[1]_1_AE2") (pintype "passive+no_connect"))
    )
    (net (code "49") (name "unconnected-(U1B-JTG_TCK_1-PadAN11)") (class "Default")
      (node (ref "U1") (pin "AN11") (pinfunction "JTG_TCK_1_AN11") (pintype "passive+no_connect"))
    )
    (net (code "50") (name "unconnected-(U1B-JTG_TDI_1-PadAT11)") (class "Default")
      (node (ref "U1") (pin "AT11") (pinfunction "JTG_TDI_1_AT11") (pintype "passive+no_connect"))
    )
    (net (code "51") (name "unconnected-(U1B-JTG_TDO_1-PadAP12)") (class "Default")
      (node (ref "U1") (pin "AP12") (pinfunction "JTG_TDO_1_AP12") (pintype "passive+no_connect"))
    )
    (net (code "52") (name "unconnected-(U1B-JTG_TMS_1-PadAT12)") (class "Default")
      (node (ref "U1") (pin "AT12") (pinfunction "JTG_TMS_1_AT12") (pintype "passive+no_connect"))
    )
    (net (code "53") (name "unconnected-(U1B-TEST_GPIO[0]_1-PadAR18)") (class "Default")
      (node (ref "U1") (pin "AR18") (pinfunction "TEST_GPIO[0]_1_AR18") (pintype "passive+no_connect"))
    )
    (net (code "54") (name "unconnected-(U1B-TEST_GPIO[1]_1-PadAR17)") (class "Default")
      (node (ref "U1") (pin "AR17") (pinfunction "TEST_GPIO[1]_1_AR17") (pintype "passive+no_connect"))
    )
    (net (code "55") (name "unconnected-(U1B-TEST_GPIO[2]_1-PadAP17)") (class "Default")
      (node (ref "U1") (pin "AP17") (pinfunction "TEST_GPIO[2]_1_AP17") (pintype "passive+no_connect"))
    )
    (net (code "56") (name "unconnected-(U1B-TEST_GPIO[3]_1-PadAT17)") (class "Default")
      (node (ref "U1") (pin "AT17") (pinfunction "TEST_GPIO[3]_1_AT17") (pintype "passive+no_connect"))
    )
    (net (code "57") (name "unconnected-(U1B-TEST_GPIO[4]_1-PadAN16)") (class "Default")
      (node (ref "U1") (pin "AN16") (pinfunction "TEST_GPIO[4]_1_AN16") (pintype "passive+no_connect"))
    )
    (net (code "58") (name "unconnected-(U1B-TEST_GPIO[5]_1-PadAT16)") (class "Default")
      (node (ref "U1") (pin "AT16") (pinfunction "TEST_GPIO[5]_1_AT16") (pintype "passive+no_connect"))
    )
    (net (code "59") (name "unconnected-(U1B-TEST_GPIO[6]_1-PadAP16)") (class "Default")
      (node (ref "U1") (pin "AP16") (pinfunction "TEST_GPIO[6]_1_AP16") (pintype "passive+no_connect"))
    )
    (net (code "60") (name "unconnected-(U1B-TEST_GPIO[7]_1-PadAN15)") (class "Default")
      (node (ref "U1") (pin "AN15") (pinfunction "TEST_GPIO[7]_1_AN15") (pintype "passive+no_connect"))
    )
    (net (code "61") (name "unconnected-(U1B-TEST_GPIO[8]_1-PadAP15)") (class "Default")
      (node (ref "U1") (pin "AP15") (pinfunction "TEST_GPIO[8]_1_AP15") (pintype "passive+no_connect"))
    )
    (net (code "62") (name "unconnected-(U1B-TEST_GPIO[9]_1-PadAT15)") (class "Default")
      (node (ref "U1") (pin "AT15") (pinfunction "TEST_GPIO[9]_1_AT15") (pintype "passive+no_connect"))
    )
    (net (code "63") (name "unconnected-(U1B-TEST_GPIO[10]_1-PadAR15)") (class "Default")
      (node (ref "U1") (pin "AR15") (pinfunction "TEST_GPIO[10]_1_AR15") (pintype "passive+no_connect"))
    )
    (net (code "64") (name "unconnected-(U1B-TEST_GPIO[11]_1-PadAN14)") (class "Default")
      (node (ref "U1") (pin "AN14") (pinfunction "TEST_GPIO[11]_1_AN14") (pintype "passive+no_connect"))
    )
    (net (code "65") (name "unconnected-(U1B-TEST_GPIO[12]_1-PadAR14)") (class "Default")
      (node (ref "U1") (pin "AR14") (pinfunction "TEST_GPIO[12]_1_AR14") (pintype "passive+no_connect"))
    )
    (net (code "66") (name "unconnected-(U1B-TEST_GPIO[13]_1-PadAR13)") (class "Default")
      (node (ref "U1") (pin "AR13") (pinfunction "TEST_GPIO[13]_1_AR13") (pintype "passive+no_connect"))
    )
    (net (code "67") (name "unconnected-(U1B-TEST_GPIO[14]_1-PadAT14)") (class "Default")
      (node (ref "U1") (pin "AT14") (pinfunction "TEST_GPIO[14]_1_AT14") (pintype "passive+no_connect"))
    )
    (net (code "68") (name "unconnected-(U1B-TEST_GPIO[15]_1-PadAP13)") (class "Default")
      (node (ref "U1") (pin "AP13") (pinfunction "TEST_GPIO[15]_1_AP13") (pintype "passive+no_connect"))
    )
    (net (code "69") (name "unconnected-(U1B-TEST_GPIO[16]_1-PadAP11)") (class "Default")
      (node (ref "U1") (pin "AP11") (pinfunction "TEST_GPIO[16]_1_AP11") (pintype "passive+no_connect"))
    )
    (net (code "70") (name "unconnected-(U1B-TEST_GPIO[17]_1-PadAT10)") (class "Default")
      (node (ref "U1") (pin "AT10") (pinfunction "TEST_GPIO[17]_1_AT10") (pintype "passive+no_connect"))
    )
    (net (code "71") (name "unconnected-(U1B-TEST_GPIO[18]_1-PadAR10)") (class "Default")
      (node (ref "U1") (pin "AR10") (pinfunction "TEST_GPIO[18]_1_AR10") (pintype "passive+no_connect"))
    )
    (net (code "72") (name "unconnected-(U1B-TEST_GPIO[19]_1-PadAN10)") (class "Default")
      (node (ref "U1") (pin "AN10") (pinfunction "TEST_GPIO[19]_1_AN10") (pintype "passive+no_connect"))
    )
    (net (code "73") (name "unconnected-(U1B-TEST_GPIO[20]_1-PadAP10)") (class "Default")
      (node (ref "U1") (pin "AP10") (pinfunction "TEST_GPIO[20]_1_AP10") (pintype "passive+no_connect"))
    )
    (net (code "74") (name "unconnected-(U1B-TEST_GPIO[21]_1-PadAT9)") (class "Default")
      (node (ref "U1") (pin "AT9") (pinfunction "TEST_GPIO[21]_1_AT9") (pintype "passive+no_connect"))
    )
    (net (code "75") (name "unconnected-(U1B-TEST_GPIO[22]_1-PadAR9)") (class "Default")
      (node (ref "U1") (pin "AR9") (pinfunction "TEST_GPIO[22]_1_AR9") (pintype "passive+no_connect"))
    )
    (net (code "76") (name "unconnected-(U1B-TEST_GPIO[23]_1-PadAR8)") (class "Default")
      (node (ref "U1") (pin "AR8") (pinfunction "TEST_GPIO[23]_1_AR8") (pintype "passive+no_connect"))
    )
    (net (code "77") (name "unconnected-(U1B-TEST_GPIO[24]_1-PadAN9)") (class "Default")
      (node (ref "U1") (pin "AN9") (pinfunction "TEST_GPIO[24]_1_AN9") (pintype "passive+no_connect"))
    )
    (net (code "78") (name "unconnected-(U1B-TEST_GPIO[25]_1-PadAP8)") (class "Default")
      (node (ref "U1") (pin "AP8") (pinfunction "TEST_GPIO[25]_1_AP8") (pintype "passive+no_connect"))
    )
    (net (code "79") (name "unconnected-(U1B-TEST_GPIO[26]_1-PadAN8)") (class "Default")
      (node (ref "U1") (pin "AN8") (pinfunction "TEST_GPIO[26]_1_AN8") (pintype "passive+no_connect"))
    )
    (net (code "80") (name "unconnected-(U1B-TEST_GPIO[27]_1-PadAR7)") (class "Default")
      (node (ref "U1") (pin "AR7") (pinfunction "TEST_GPIO[27]_1_AR7") (pintype "passive+no_connect"))
    )
    (net (code "81") (name "unconnected-(U1B-TEST_GPIO[28]_1-PadAT7)") (class "Default")
      (node (ref "U1") (pin "AT7") (pinfunction "TEST_GPIO[28]_1_AT7") (pintype "passive+no_connect"))
    )
    (net (code "82") (name "unconnected-(U1B-TEST_GPIO[29]_1-PadAP7)") (class "Default")
      (node (ref "U1") (pin "AP7") (pinfunction "TEST_GPIO[29]_1_AP7") (pintype "passive+no_connect"))
    )
    (net (code "83") (name "unconnected-(U1B-TEST_GPIO[30]_1-PadAT6)") (class "Default")
      (node (ref "U1") (pin "AT6") (pinfunction "TEST_GPIO[30]_1_AT6") (pintype "passive+no_connect"))
    )
    (net (code "84") (name "unconnected-(U1B-TEST_GPIO[31]_1-PadAT5)") (class "Default")
      (node (ref "U1") (pin "AT5") (pinfunction "TEST_GPIO[31]_1_AT5") (pintype "passive+no_connect"))
    )
    (net (code "85") (name "unconnected-(U1B-TEST_GPIO[32]_1-PadAP6)") (class "Default")
      (node (ref "U1") (pin "AP6") (pinfunction "TEST_GPIO[32]_1_AP6") (pintype "passive+no_connect"))
    )
    (net (code "86") (name "unconnected-(U1B-TEST_GPIO[33]_1-PadAN6)") (class "Default")
      (node (ref "U1") (pin "AN6") (pinfunction "TEST_GPIO[33]_1_AN6") (pintype "passive+no_connect"))
    )
    (net (code "87") (name "unconnected-(U1B-TEST_GPIO[34]_1-PadAN5)") (class "Default")
      (node (ref "U1") (pin "AN5") (pinfunction "TEST_GPIO[34]_1_AN5") (pintype "passive+no_connect"))
    )
    (net (code "88") (name "unconnected-(U1B-TEST_GPIO[35]_1-PadAT4)") (class "Default")
      (node (ref "U1") (pin "AT4") (pinfunction "TEST_GPIO[35]_1_AT4") (pintype "passive+no_connect"))
    )
    (net (code "89") (name "unconnected-(U1B-TEST_GPIO[36]_1-PadAR4)") (class "Default")
      (node (ref "U1") (pin "AR4") (pinfunction "TEST_GPIO[36]_1_AR4") (pintype "passive+no_connect"))
    )
    (net (code "90") (name "unconnected-(U1B-TEST_GPIO[37]_1-PadAN4)") (class "Default")
      (node (ref "U1") (pin "AN4") (pinfunction "TEST_GPIO[37]_1_AN4") (pintype "passive+no_connect"))
    )
    (net (code "91") (name "unconnected-(U1B-TEST_GPIO[38]_1-PadAR3)") (class "Default")
      (node (ref "U1") (pin "AR3") (pinfunction "TEST_GPIO[38]_1_AR3") (pintype "passive+no_connect"))
    )
    (net (code "92") (name "unconnected-(U1B-TEST_GPIO[39]_1-PadAM4)") (class "Default")
      (node (ref "U1") (pin "AM4") (pinfunction "TEST_GPIO[39]_1_AM4") (pintype "passive+no_connect"))
    )
    (net (code "93") (name "unconnected-(U1B-TEST_GPIO[40]_1-PadAP3)") (class "Default")
      (node (ref "U1") (pin "AP3") (pinfunction "TEST_GPIO[40]_1_AP3") (pintype "passive+no_connect"))
    )
    (net (code "94") (name "unconnected-(U1B-TEST_GPIO[41]_1-PadAN3)") (class "Default")
      (node (ref "U1") (pin "AN3") (pinfunction "TEST_GPIO[41]_1_AN3") (pintype "passive+no_connect"))
    )
    (net (code "95") (name "unconnected-(U1B-TEST_GPIO[42]_1-PadAR2)") (class "Default")
      (node (ref "U1") (pin "AR2") (pinfunction "TEST_GPIO[42]_1_AR2") (pintype "passive+no_connect"))
    )
    (net (code "96") (name "unconnected-(U1B-TEST_GPIO[43]_1-PadAL4)") (class "Default")
      (node (ref "U1") (pin "AL4") (pinfunction "TEST_GPIO[43]_1_AL4") (pintype "passive+no_connect"))
    )
    (net (code "97") (name "unconnected-(U1B-TEST_GPIO[44]_1-PadAM3)") (class "Default")
      (node (ref "U1") (pin "AM3") (pinfunction "TEST_GPIO[44]_1_AM3") (pintype "passive+no_connect"))
    )
    (net (code "98") (name "unconnected-(U1B-TEST_GPIO[45]_1-PadAP2)") (class "Default")
      (node (ref "U1") (pin "AP2") (pinfunction "TEST_GPIO[45]_1_AP2") (pintype "passive+no_connect"))
    )
    (net (code "99") (name "unconnected-(U1B-TEST_GPIO[46]_1-PadAP1)") (class "Default")
      (node (ref "U1") (pin "AP1") (pinfunction "TEST_GPIO[46]_1_AP1") (pintype "passive+no_connect"))
    )
    (net (code "100") (name "unconnected-(U1B-TEST_GPIO[47]_1-PadAK4)") (class "Default")
      (node (ref "U1") (pin "AK4") (pinfunction "TEST_GPIO[47]_1_AK4") (pintype "passive+no_connect"))
    )
    (net (code "101") (name "unconnected-(U1B-TEST_GPIO[48]_1-PadAM2)") (class "Default")
      (node (ref "U1") (pin "AM2") (pinfunction "TEST_GPIO[48]_1_AM2") (pintype "passive+no_connect"))
    )
    (net (code "102") (name "unconnected-(U1B-TEST_GPIO[49]_1-PadAN1)") (class "Default")
      (node (ref "U1") (pin "AN1") (pinfunction "TEST_GPIO[49]_1_AN1") (pintype "passive+no_connect"))
    )
    (net (code "103") (name "unconnected-(U1B-TEST_GPIO[50]_1-PadAK3)") (class "Default")
      (node (ref "U1") (pin "AK3") (pinfunction "TEST_GPIO[50]_1_AK3") (pintype "passive+no_connect"))
    )
    (net (code "104") (name "unconnected-(U1B-TEST_GPIO[51]_1-PadAL2)") (class "Default")
      (node (ref "U1") (pin "AL2") (pinfunction "TEST_GPIO[51]_1_AL2") (pintype "passive+no_connect"))
    )
    (net (code "105") (name "unconnected-(U1B-TEST_GPIO[52]_1-PadAD3)") (class "Default")
      (node (ref "U1") (pin "AD3") (pinfunction "TEST_GPIO[52]_1_AD3") (pintype "passive+no_connect"))
    )
    (net (code "106") (name "unconnected-(U1B-TEST_GPIO[53]_1-PadAD2)") (class "Default")
      (node (ref "U1") (pin "AD2") (pinfunction "TEST_GPIO[53]_1_AD2") (pintype "passive+no_connect"))
    )
    (net (code "107") (name "unconnected-(U1B-TEST_GPIO[54]_1-PadAC3)") (class "Default")
      (node (ref "U1") (pin "AC3") (pinfunction "TEST_GPIO[54]_1_AC3") (pintype "passive+no_connect"))
    )
    (net (code "108") (name "unconnected-(U1B-TEST_GPIO[55]_1-PadAC4)") (class "Default")
      (node (ref "U1") (pin "AC4") (pinfunction "TEST_GPIO[55]_1_AC4") (pintype "passive+no_connect"))
    )
    (net (code "109") (name "unconnected-(U1B-TEST_GPIO[56]_1-PadAD1)") (class "Default")
      (node (ref "U1") (pin "AD1") (pinfunction "TEST_GPIO[56]_1_AD1") (pintype "passive+no_connect"))
    )
    (net (code "110") (name "unconnected-(U1B-TEST_GPIO[57]_1-PadAC1)") (class "Default")
      (node (ref "U1") (pin "AC1") (pinfunction "TEST_GPIO[57]_1_AC1") (pintype "passive+no_connect"))
    )
    (net (code "111") (name "unconnected-(U1B-TEST_GPIO[58]_1-PadAB3)") (class "Default")
      (node (ref "U1") (pin "AB3") (pinfunction "TEST_GPIO[58]_1_AB3") (pintype "passive+no_connect"))
    )
    (net (code "112") (name "unconnected-(U1B-TEST_GPIO[59]_1-PadAB4)") (class "Default")
      (node (ref "U1") (pin "AB4") (pinfunction "TEST_GPIO[59]_1_AB4") (pintype "passive+no_connect"))
    )
    (net (code "113") (name "unconnected-(U1B-TEST_GPIO[60]_1-PadAB2)") (class "Default")
      (node (ref "U1") (pin "AB2") (pinfunction "TEST_GPIO[60]_1_AB2") (pintype "passive+no_connect"))
    )
    (net (code "114") (name "unconnected-(U1B-TEST_GPIO[61]_1-PadAA1)") (class "Default")
      (node (ref "U1") (pin "AA1") (pinfunction "TEST_GPIO[61]_1_AA1") (pintype "passive+no_connect"))
    )
    (net (code "115") (name "unconnected-(U1B-TEST_GPIO[62]_1-PadAB1)") (class "Default")
      (node (ref "U1") (pin "AB1") (pinfunction "TEST_GPIO[62]_1_AB1") (pintype "passive+no_connect"))
    )
    (net (code "116") (name "unconnected-(U1B-TEST_GPIO[63]_1-PadAA2)") (class "Default")
      (node (ref "U1") (pin "AA2") (pinfunction "TEST_GPIO[63]_1_AA2") (pintype "passive+no_connect"))
    )
    (net (code "117") (name "unconnected-(U1B-TEST_GPIO[64]_1-PadAA4)") (class "Default")
      (node (ref "U1") (pin "AA4") (pinfunction "TEST_GPIO[64]_1_AA4") (pintype "passive+no_connect"))
    )
    (net (code "118") (name "unconnected-(U1B-TEST_GPIO[65]_1-PadY3)") (class "Default")
      (node (ref "U1") (pin "Y3") (pinfunction "TEST_GPIO[65]_1_Y3") (pintype "passive+no_connect"))
    )
    (net (code "119") (name "unconnected-(U1B-TEST_GPIO[66]_1-PadY2)") (class "Default")
      (node (ref "U1") (pin "Y2") (pinfunction "TEST_GPIO[66]_1_Y2") (pintype "passive+no_connect"))
    )
    (net (code "120") (name "unconnected-(U1B-TEST_GPIO[67]_1-PadY4)") (class "Default")
      (node (ref "U1") (pin "Y4") (pinfunction "TEST_GPIO[67]_1_Y4") (pintype "passive+no_connect"))
    )
    (net (code "121") (name "unconnected-(U1B-TEST_GPIO[68]_1-PadW1)") (class "Default")
      (node (ref "U1") (pin "W1") (pinfunction "TEST_GPIO[68]_1_W1") (pintype "passive+no_connect"))
    )
    (net (code "122") (name "unconnected-(U1B-TEST_GPIO[69]_1-PadW3)") (class "Default")
      (node (ref "U1") (pin "W3") (pinfunction "TEST_GPIO[69]_1_W3") (pintype "passive+no_connect"))
    )
    (net (code "123") (name "unconnected-(U1B-TEST_GPIO[70]_1-PadW2)") (class "Default")
      (node (ref "U1") (pin "W2") (pinfunction "TEST_GPIO[70]_1_W2") (pintype "passive+no_connect"))
    )
    (net (code "124") (name "unconnected-(U1B-TEST_GPIO[71]_1-PadW5)") (class "Default")
      (node (ref "U1") (pin "W5") (pinfunction "TEST_GPIO[71]_1_W5") (pintype "passive+no_connect"))
    )
    (net (code "125") (name "unconnected-(U1C-DBG_SPARE[0]_2-PadAP25)") (class "Default")
      (node (ref "U1") (pin "AP25") (pinfunction "DBG_SPARE[0]_2_AP25") (pintype "passive+no_connect"))
    )
    (net (code "126") (name "unconnected-(U1C-DBG_SPARE[1]_2-PadAR25)") (class "Default")
      (node (ref "U1") (pin "AR25") (pinfunction "DBG_SPARE[1]_2_AR25") (pintype "passive+no_connect"))
    )
    (net (code "127") (name "unconnected-(U1C-JTG_TCK_2-PadAF33)") (class "Default")
      (node (ref "U1") (pin "AF33") (pinfunction "JTG_TCK_2_AF33") (pintype "passive+no_connect"))
    )
    (net (code "128") (name "unconnected-(U1C-JTG_TDI_2-PadAF36)") (class "Default")
      (node (ref "U1") (pin "AF36") (pinfunction "JTG_TDI_2_AF36") (pintype "passive+no_connect"))
    )
    (net (code "129") (name "unconnected-(U1C-JTG_TDO_2-PadAE34)") (class "Default")
      (node (ref "U1") (pin "AE34") (pinfunction "JTG_TDO_2_AE34") (pintype "passive+no_connect"))
    )
    (net (code "130") (name "unconnected-(U1C-JTG_TMS_2-PadAE36)") (class "Default")
      (node (ref "U1") (pin "AE36") (pinfunction "JTG_TMS_2_AE36") (pintype "passive+no_connect"))
    )
    (net (code "131") (name "unconnected-(U1C-TEST_GPIO[0]_2-PadW35)") (class "Default")
      (node (ref "U1") (pin "W35") (pinfunction "TEST_GPIO[0]_2_W35") (pintype "passive+no_connect"))
    )
    (net (code "132") (name "unconnected-(U1C-TEST_GPIO[1]_2-PadY35)") (class "Default")
      (node (ref "U1") (pin "Y35") (pinfunction "TEST_GPIO[1]_2_Y35") (pintype "passive+no_connect"))
    )
    (net (code "133") (name "unconnected-(U1C-TEST_GPIO[2]_2-PadY34)") (class "Default")
      (node (ref "U1") (pin "Y34") (pinfunction "TEST_GPIO[2]_2_Y34") (pintype "passive+no_connect"))
    )
    (net (code "134") (name "unconnected-(U1C-TEST_GPIO[3]_2-PadY36)") (class "Default")
      (node (ref "U1") (pin "Y36") (pinfunction "TEST_GPIO[3]_2_Y36") (pintype "passive+no_connect"))
    )
    (net (code "135") (name "unconnected-(U1C-TEST_GPIO[4]_2-PadAA33)") (class "Default")
      (node (ref "U1") (pin "AA33") (pinfunction "TEST_GPIO[4]_2_AA33") (pintype "passive+no_connect"))
    )
    (net (code "136") (name "unconnected-(U1C-TEST_GPIO[5]_2-PadAA36)") (class "Default")
      (node (ref "U1") (pin "AA36") (pinfunction "TEST_GPIO[5]_2_AA36") (pintype "passive+no_connect"))
    )
    (net (code "137") (name "unconnected-(U1C-TEST_GPIO[6]_2-PadAA34)") (class "Default")
      (node (ref "U1") (pin "AA34") (pinfunction "TEST_GPIO[6]_2_AA34") (pintype "passive+no_connect"))
    )
    (net (code "138") (name "unconnected-(U1C-TEST_GPIO[7]_2-PadAB33)") (class "Default")
      (node (ref "U1") (pin "AB33") (pinfunction "TEST_GPIO[7]_2_AB33") (pintype "passive+no_connect"))
    )
    (net (code "139") (name "unconnected-(U1C-TEST_GPIO[8]_2-PadAB34)") (class "Default")
      (node (ref "U1") (pin "AB34") (pinfunction "TEST_GPIO[8]_2_AB34") (pintype "passive+no_connect"))
    )
    (net (code "140") (name "unconnected-(U1C-TEST_GPIO[9]_2-PadAB36)") (class "Default")
      (node (ref "U1") (pin "AB36") (pinfunction "TEST_GPIO[9]_2_AB36") (pintype "passive+no_connect"))
    )
    (net (code "141") (name "unconnected-(U1C-TEST_GPIO[10]_2-PadAB35)") (class "Default")
      (node (ref "U1") (pin "AB35") (pinfunction "TEST_GPIO[10]_2_AB35") (pintype "passive+no_connect"))
    )
    (net (code "142") (name "unconnected-(U1C-TEST_GPIO[11]_2-PadAC33)") (class "Default")
      (node (ref "U1") (pin "AC33") (pinfunction "TEST_GPIO[11]_2_AC33") (pintype "passive+no_connect"))
    )
    (net (code "143") (name "unconnected-(U1C-TEST_GPIO[12]_2-PadAC35)") (class "Default")
      (node (ref "U1") (pin "AC35") (pinfunction "TEST_GPIO[12]_2_AC35") (pintype "passive+no_connect"))
    )
    (net (code "144") (name "unconnected-(U1C-TEST_GPIO[13]_2-PadAD35)") (class "Default")
      (node (ref "U1") (pin "AD35") (pinfunction "TEST_GPIO[13]_2_AD35") (pintype "passive+no_connect"))
    )
    (net (code "145") (name "unconnected-(U1C-TEST_GPIO[14]_2-PadAC36)") (class "Default")
      (node (ref "U1") (pin "AC36") (pinfunction "TEST_GPIO[14]_2_AC36") (pintype "passive+no_connect"))
    )
    (net (code "146") (name "unconnected-(U1C-TEST_GPIO[15]_2-PadAD34)") (class "Default")
      (node (ref "U1") (pin "AD34") (pinfunction "TEST_GPIO[15]_2_AD34") (pintype "passive+no_connect"))
    )
    (net (code "147") (name "unconnected-(U1C-TEST_GPIO[16]_2-PadAF34)") (class "Default")
      (node (ref "U1") (pin "AF34") (pinfunction "TEST_GPIO[16]_2_AF34") (pintype "passive+no_connect"))
    )
    (net (code "148") (name "unconnected-(U1C-TEST_GPIO[17]_2-PadAG36)") (class "Default")
      (node (ref "U1") (pin "AG36") (pinfunction "TEST_GPIO[17]_2_AG36") (pintype "passive+no_connect"))
    )
    (net (code "149") (name "unconnected-(U1C-TEST_GPIO[18]_2-PadAG35)") (class "Default")
      (node (ref "U1") (pin "AG35") (pinfunction "TEST_GPIO[18]_2_AG35") (pintype "passive+no_connect"))
    )
    (net (code "150") (name "unconnected-(U1C-TEST_GPIO[19]_2-PadAG33)") (class "Default")
      (node (ref "U1") (pin "AG33") (pinfunction "TEST_GPIO[19]_2_AG33") (pintype "passive+no_connect"))
    )
    (net (code "151") (name "unconnected-(U1C-TEST_GPIO[20]_2-PadAG34)") (class "Default")
      (node (ref "U1") (pin "AG34") (pinfunction "TEST_GPIO[20]_2_AG34") (pintype "passive+no_connect"))
    )
    (net (code "152") (name "unconnected-(U1C-TEST_GPIO[21]_2-PadAH36)") (class "Default")
      (node (ref "U1") (pin "AH36") (pinfunction "TEST_GPIO[21]_2_AH36") (pintype "passive+no_connect"))
    )
    (net (code "153") (name "unconnected-(U1C-TEST_GPIO[22]_2-PadAH35)") (class "Default")
      (node (ref "U1") (pin "AH35") (pinfunction "TEST_GPIO[22]_2_AH35") (pintype "passive+no_connect"))
    )
    (net (code "154") (name "unconnected-(U1C-TEST_GPIO[23]_2-PadAJ35)") (class "Default")
      (node (ref "U1") (pin "AJ35") (pinfunction "TEST_GPIO[23]_2_AJ35") (pintype "passive+no_connect"))
    )
    (net (code "155") (name "unconnected-(U1C-TEST_GPIO[24]_2-PadAH33)") (class "Default")
      (node (ref "U1") (pin "AH33") (pinfunction "TEST_GPIO[24]_2_AH33") (pintype "passive+no_connect"))
    )
    (net (code "156") (name "unconnected-(U1C-TEST_GPIO[25]_2-PadAJ34)") (class "Default")
      (node (ref "U1") (pin "AJ34") (pinfunction "TEST_GPIO[25]_2_AJ34") (pintype "passive+no_connect"))
    )
    (net (code "157") (name "unconnected-(U1C-TEST_GPIO[26]_2-PadAJ33)") (class "Default")
      (node (ref "U1") (pin "AJ33") (pinfunction "TEST_GPIO[26]_2_AJ33") (pintype "passive+no_connect"))
    )
    (net (code "158") (name "unconnected-(U1C-TEST_GPIO[27]_2-PadAK35)") (class "Default")
      (node (ref "U1") (pin "AK35") (pinfunction "TEST_GPIO[27]_2_AK35") (pintype "passive+no_connect"))
    )
    (net (code "159") (name "unconnected-(U1C-TEST_GPIO[28]_2-PadAK36)") (class "Default")
      (node (ref "U1") (pin "AK36") (pinfunction "TEST_GPIO[28]_2_AK36") (pintype "passive+no_connect"))
    )
    (net (code "160") (name "unconnected-(U1C-TEST_GPIO[29]_2-PadAK34)") (class "Default")
      (node (ref "U1") (pin "AK34") (pinfunction "TEST_GPIO[29]_2_AK34") (pintype "passive+no_connect"))
    )
    (net (code "161") (name "unconnected-(U1C-TEST_GPIO[30]_2-PadAL36)") (class "Default")
      (node (ref "U1") (pin "AL36") (pinfunction "TEST_GPIO[30]_2_AL36") (pintype "passive+no_connect"))
    )
    (net (code "162") (name "unconnected-(U1C-TEST_GPIO[31]_2-PadAM36)") (class "Default")
      (node (ref "U1") (pin "AM36") (pinfunction "TEST_GPIO[31]_2_AM36") (pintype "passive+no_connect"))
    )
    (net (code "163") (name "unconnected-(U1C-TEST_GPIO[32]_2-PadAL34)") (class "Default")
      (node (ref "U1") (pin "AL34") (pinfunction "TEST_GPIO[32]_2_AL34") (pintype "passive+no_connect"))
    )
    (net (code "164") (name "unconnected-(U1C-TEST_GPIO[33]_2-PadAL33)") (class "Default")
      (node (ref "U1") (pin "AL33") (pinfunction "TEST_GPIO[33]_2_AL33") (pintype "passive+no_connect"))
    )
    (net (code "165") (name "unconnected-(U1C-TEST_GPIO[34]_2-PadAM33)") (class "Default")
      (node (ref "U1") (pin "AM33") (pinfunction "TEST_GPIO[34]_2_AM33") (pintype "passive+no_connect"))
    )
    (net (code "166") (name "unconnected-(U1C-TEST_GPIO[35]_2-PadAN36)") (class "Default")
      (node (ref "U1") (pin "AN36") (pinfunction "TEST_GPIO[35]_2_AN36") (pintype "passive+no_connect"))
    )
    (net (code "167") (name "unconnected-(U1C-TEST_GPIO[36]_2-PadAN35)") (class "Default")
      (node (ref "U1") (pin "AN35") (pinfunction "TEST_GPIO[36]_2_AN35") (pintype "passive+no_connect"))
    )
    (net (code "168") (name "unconnected-(U1C-TEST_GPIO[37]_2-PadAN33)") (class "Default")
      (node (ref "U1") (pin "AN33") (pinfunction "TEST_GPIO[37]_2_AN33") (pintype "passive+no_connect"))
    )
    (net (code "169") (name "unconnected-(U1C-TEST_GPIO[38]_2-PadAP35)") (class "Default")
      (node (ref "U1") (pin "AP35") (pinfunction "TEST_GPIO[38]_2_AP35") (pintype "passive+no_connect"))
    )
    (net (code "170") (name "unconnected-(U1C-TEST_GPIO[39]_2-PadAN32)") (class "Default")
      (node (ref "U1") (pin "AN32") (pinfunction "TEST_GPIO[39]_2_AN32") (pintype "passive+no_connect"))
    )
    (net (code "171") (name "unconnected-(U1C-TEST_GPIO[40]_2-PadAP34)") (class "Default")
      (node (ref "U1") (pin "AP34") (pinfunction "TEST_GPIO[40]_2_AP34") (pintype "passive+no_connect"))
    )
    (net (code "172") (name "unconnected-(U1C-TEST_GPIO[41]_2-PadAP33)") (class "Default")
      (node (ref "U1") (pin "AP33") (pinfunction "TEST_GPIO[41]_2_AP33") (pintype "passive+no_connect"))
    )
    (net (code "173") (name "unconnected-(U1C-TEST_GPIO[42]_2-PadAR35)") (class "Default")
      (node (ref "U1") (pin "AR35") (pinfunction "TEST_GPIO[42]_2_AR35") (pintype "passive+no_connect"))
    )
    (net (code "174") (name "unconnected-(U1C-TEST_GPIO[43]_2-PadAN31)") (class "Default")
      (node (ref "U1") (pin "AN31") (pinfunction "TEST_GPIO[43]_2_AN31") (pintype "passive+no_connect"))
    )
    (net (code "175") (name "unconnected-(U1C-TEST_GPIO[44]_2-PadAP32)") (class "Default")
      (node (ref "U1") (pin "AP32") (pinfunction "TEST_GPIO[44]_2_AP32") (pintype "passive+no_connect"))
    )
    (net (code "176") (name "unconnected-(U1C-TEST_GPIO[45]_2-PadAR34)") (class "Default")
      (node (ref "U1") (pin "AR34") (pinfunction "TEST_GPIO[45]_2_AR34") (pintype "passive+no_connect"))
    )
    (net (code "177") (name "unconnected-(U1C-TEST_GPIO[46]_2-PadAT34)") (class "Default")
      (node (ref "U1") (pin "AT34") (pinfunction "TEST_GPIO[46]_2_AT34") (pintype "passive+no_connect"))
    )
    (net (code "178") (name "unconnected-(U1C-TEST_GPIO[47]_2-PadAN30)") (class "Default")
      (node (ref "U1") (pin "AN30") (pinfunction "TEST_GPIO[47]_2_AN30") (pintype "passive+no_connect"))
    )
    (net (code "179") (name "unconnected-(U1C-TEST_GPIO[48]_2-PadAR32)") (class "Default")
      (node (ref "U1") (pin "AR32") (pinfunction "TEST_GPIO[48]_2_AR32") (pintype "passive+no_connect"))
    )
    (net (code "180") (name "unconnected-(U1C-TEST_GPIO[49]_2-PadAT33)") (class "Default")
      (node (ref "U1") (pin "AT33") (pinfunction "TEST_GPIO[49]_2_AT33") (pintype "passive+no_connect"))
    )
    (net (code "181") (name "unconnected-(U1C-TEST_GPIO[50]_2-PadAP30)") (class "Default")
      (node (ref "U1") (pin "AP30") (pinfunction "TEST_GPIO[50]_2_AP30") (pintype "passive+no_connect"))
    )
    (net (code "182") (name "unconnected-(U1C-TEST_GPIO[51]_2-PadAR31)") (class "Default")
      (node (ref "U1") (pin "AR31") (pinfunction "TEST_GPIO[51]_2_AR31") (pintype "passive+no_connect"))
    )
    (net (code "183") (name "unconnected-(U1C-TEST_GPIO[52]_2-PadAP24)") (class "Default")
      (node (ref "U1") (pin "AP24") (pinfunction "TEST_GPIO[52]_2_AP24") (pintype "passive+no_connect"))
    )
    (net (code "184") (name "unconnected-(U1C-TEST_GPIO[53]_2-PadAR24)") (class "Default")
      (node (ref "U1") (pin "AR24") (pinfunction "TEST_GPIO[53]_2_AR24") (pintype "passive+no_connect"))
    )
    (net (code "185") (name "unconnected-(U1C-TEST_GPIO[54]_2-PadAP23)") (class "Default")
      (node (ref "U1") (pin "AP23") (pinfunction "TEST_GPIO[54]_2_AP23") (pintype "passive+no_connect"))
    )
    (net (code "186") (name "unconnected-(U1C-TEST_GPIO[55]_2-PadAN23)") (class "Default")
      (node (ref "U1") (pin "AN23") (pinfunction "TEST_GPIO[55]_2_AN23") (pintype "passive+no_connect"))
    )
    (net (code "187") (name "unconnected-(U1C-TEST_GPIO[56]_2-PadAT24)") (class "Default")
      (node (ref "U1") (pin "AT24") (pinfunction "TEST_GPIO[56]_2_AT24") (pintype "passive+no_connect"))
    )
    (net (code "188") (name "unconnected-(U1C-TEST_GPIO[57]_2-PadAT23)") (class "Default")
      (node (ref "U1") (pin "AT23") (pinfunction "TEST_GPIO[57]_2_AT23") (pintype "passive+no_connect"))
    )
    (net (code "189") (name "unconnected-(U1C-TEST_GPIO[58]_2-PadAP22)") (class "Default")
      (node (ref "U1") (pin "AP22") (pinfunction "TEST_GPIO[58]_2_AP22") (pintype "passive+no_connect"))
    )
    (net (code "190") (name "unconnected-(U1C-TEST_GPIO[59]_2-PadAN22)") (class "Default")
      (node (ref "U1") (pin "AN22") (pinfunction "TEST_GPIO[59]_2_AN22") (pintype "passive+no_connect"))
    )
    (net (code "191") (name "unconnected-(U1C-TEST_GPIO[60]_2-PadAR22)") (class "Default")
      (node (ref "U1") (pin "AR22") (pinfunction "TEST_GPIO[60]_2_AR22") (pintype "passive+no_connect"))
    )
    (net (code "192") (name "unconnected-(U1C-TEST_GPIO[61]_2-PadAT21)") (class "Default")
      (node (ref "U1") (pin "AT21") (pinfunction "TEST_GPIO[61]_2_AT21") (pintype "passive+no_connect"))
    )
    (net (code "193") (name "unconnected-(U1C-TEST_GPIO[62]_2-PadAT22)") (class "Default")
      (node (ref "U1") (pin "AT22") (pinfunction "TEST_GPIO[62]_2_AT22") (pintype "passive+no_connect"))
    )
    (net (code "194") (name "unconnected-(U1C-TEST_GPIO[63]_2-PadAR21)") (class "Default")
      (node (ref "U1") (pin "AR21") (pinfunction "TEST_GPIO[63]_2_AR21") (pintype "passive+no_connect"))
    )
    (net (code "195") (name "unconnected-(U1C-TEST_GPIO[64]_2-PadAN21)") (class "Default")
      (node (ref "U1") (pin "AN21") (pinfunction "TEST_GPIO[64]_2_AN21") (pintype "passive+no_connect"))
    )
    (net (code "196") (name "unconnected-(U1C-TEST_GPIO[65]_2-PadAP20)") (class "Default")
      (node (ref "U1") (pin "AP20") (pinfunction "TEST_GPIO[65]_2_AP20") (pintype "passive+no_connect"))
    )
    (net (code "197") (name "unconnected-(U1C-TEST_GPIO[66]_2-PadAR20)") (class "Default")
      (node (ref "U1") (pin "AR20") (pinfunction "TEST_GPIO[66]_2_AR20") (pintype "passive+no_connect"))
    )
    (net (code "198") (name "unconnected-(U1C-TEST_GPIO[67]_2-PadAN20)") (class "Default")
      (node (ref "U1") (pin "AN20") (pinfunction "TEST_GPIO[67]_2_AN20") (pintype "passive+no_connect"))
    )
    (net (code "199") (name "unconnected-(U1C-TEST_GPIO[68]_2-PadAT19)") (class "Default")
      (node (ref "U1") (pin "AT19") (pinfunction "TEST_GPIO[68]_2_AT19") (pintype "passive+no_connect"))
    )
    (net (code "200") (name "unconnected-(U1C-TEST_GPIO[69]_2-PadAP19)") (class "Default")
      (node (ref "U1") (pin "AP19") (pinfunction "TEST_GPIO[69]_2_AP19") (pintype "passive+no_connect"))
    )
    (net (code "201") (name "unconnected-(U1C-TEST_GPIO[70]_2-PadAR19)") (class "Default")
      (node (ref "U1") (pin "AR19") (pinfunction "TEST_GPIO[70]_2_AR19") (pintype "passive+no_connect"))
    )
    (net (code "202") (name "unconnected-(U1C-TEST_GPIO[71]_2-PadAM19)") (class "Default")
      (node (ref "U1") (pin "AM19") (pinfunction "TEST_GPIO[71]_2_AM19") (pintype "passive+no_connect"))
    )
    (net (code "203") (name "unconnected-(U1D-DBG_SPARE[0]_3-PadM34)") (class "Default")
      (node (ref "U1") (pin "M34") (pinfunction "DBG_SPARE[0]_3_M34") (pintype "passive+no_connect"))
    )
    (net (code "204") (name "unconnected-(U1D-DBG_SPARE[1]_3-PadM35)") (class "Default")
      (node (ref "U1") (pin "M35") (pinfunction "DBG_SPARE[1]_3_M35") (pintype "passive+no_connect"))
    )
    (net (code "205") (name "unconnected-(U1D-JTG_TCK_3-PadD26)") (class "Default")
      (node (ref "U1") (pin "D26") (pinfunction "JTG_TCK_3_D26") (pintype "passive+no_connect"))
    )
    (net (code "206") (name "unconnected-(U1D-JTG_TDI_3-PadA26)") (class "Default")
      (node (ref "U1") (pin "A26") (pinfunction "JTG_TDI_3_A26") (pintype "passive+no_connect"))
    )
    (net (code "207") (name "unconnected-(U1D-JTG_TDO_3-PadC25)") (class "Default")
      (node (ref "U1") (pin "C25") (pinfunction "JTG_TDO_3_C25") (pintype "passive+no_connect"))
    )
    (net (code "208") (name "unconnected-(U1D-JTG_TMS_3-PadA25)") (class "Default")
      (node (ref "U1") (pin "A25") (pinfunction "JTG_TMS_3_A25") (pintype "passive+no_connect"))
    )
    (net (code "209") (name "unconnected-(U1D-TEST_GPIO[0]_3-PadB19)") (class "Default")
      (node (ref "U1") (pin "B19") (pinfunction "TEST_GPIO[0]_3_B19") (pintype "passive+no_connect"))
    )
    (net (code "210") (name "unconnected-(U1D-TEST_GPIO[1]_3-PadB20)") (class "Default")
      (node (ref "U1") (pin "B20") (pinfunction "TEST_GPIO[1]_3_B20") (pintype "passive+no_connect"))
    )
    (net (code "211") (name "unconnected-(U1D-TEST_GPIO[2]_3-PadC20)") (class "Default")
      (node (ref "U1") (pin "C20") (pinfunction "TEST_GPIO[2]_3_C20") (pintype "passive+no_connect"))
    )
    (net (code "212") (name "unconnected-(U1D-TEST_GPIO[3]_3-PadA20)") (class "Default")
      (node (ref "U1") (pin "A20") (pinfunction "TEST_GPIO[3]_3_A20") (pintype "passive+no_connect"))
    )
    (net (code "213") (name "unconnected-(U1D-TEST_GPIO[4]_3-PadD21)") (class "Default")
      (node (ref "U1") (pin "D21") (pinfunction "TEST_GPIO[4]_3_D21") (pintype "passive+no_connect"))
    )
    (net (code "214") (name "unconnected-(U1D-TEST_GPIO[5]_3-PadA21)") (class "Default")
      (node (ref "U1") (pin "A21") (pinfunction "TEST_GPIO[5]_3_A21") (pintype "passive+no_connect"))
    )
    (net (code "215") (name "unconnected-(U1D-TEST_GPIO[6]_3-PadC21)") (class "Default")
      (node (ref "U1") (pin "C21") (pinfunction "TEST_GPIO[6]_3_C21") (pintype "passive+no_connect"))
    )
    (net (code "216") (name "unconnected-(U1D-TEST_GPIO[7]_3-PadD22)") (class "Default")
      (node (ref "U1") (pin "D22") (pinfunction "TEST_GPIO[7]_3_D22") (pintype "passive+no_connect"))
    )
    (net (code "217") (name "unconnected-(U1D-TEST_GPIO[8]_3-PadC22)") (class "Default")
      (node (ref "U1") (pin "C22") (pinfunction "TEST_GPIO[8]_3_C22") (pintype "passive+no_connect"))
    )
    (net (code "218") (name "unconnected-(U1D-TEST_GPIO[9]_3-PadA22)") (class "Default")
      (node (ref "U1") (pin "A22") (pinfunction "TEST_GPIO[9]_3_A22") (pintype "passive+no_connect"))
    )
    (net (code "219") (name "unconnected-(U1D-TEST_GPIO[10]_3-PadB22)") (class "Default")
      (node (ref "U1") (pin "B22") (pinfunction "TEST_GPIO[10]_3_B22") (pintype "passive+no_connect"))
    )
    (net (code "220") (name "unconnected-(U1D-TEST_GPIO[11]_3-PadD23)") (class "Default")
      (node (ref "U1") (pin "D23") (pinfunction "TEST_GPIO[11]_3_D23") (pintype "passive+no_connect"))
    )
    (net (code "221") (name "unconnected-(U1D-TEST_GPIO[12]_3-PadB23)") (class "Default")
      (node (ref "U1") (pin "B23") (pinfunction "TEST_GPIO[12]_3_B23") (pintype "passive+no_connect"))
    )
    (net (code "222") (name "unconnected-(U1D-TEST_GPIO[13]_3-PadB24)") (class "Default")
      (node (ref "U1") (pin "B24") (pinfunction "TEST_GPIO[13]_3_B24") (pintype "passive+no_connect"))
    )
    (net (code "223") (name "unconnected-(U1D-TEST_GPIO[14]_3-PadA23)") (class "Default")
      (node (ref "U1") (pin "A23") (pinfunction "TEST_GPIO[14]_3_A23") (pintype "passive+no_connect"))
    )
    (net (code "224") (name "unconnected-(U1D-TEST_GPIO[15]_3-PadC24)") (class "Default")
      (node (ref "U1") (pin "C24") (pinfunction "TEST_GPIO[15]_3_C24") (pintype "passive+no_connect"))
    )
    (net (code "225") (name "unconnected-(U1D-TEST_GPIO[16]_3-PadC26)") (class "Default")
      (node (ref "U1") (pin "C26") (pinfunction "TEST_GPIO[16]_3_C26") (pintype "passive+no_connect"))
    )
    (net (code "226") (name "unconnected-(U1D-TEST_GPIO[17]_3-PadA27)") (class "Default")
      (node (ref "U1") (pin "A27") (pinfunction "TEST_GPIO[17]_3_A27") (pintype "passive+no_connect"))
    )
    (net (code "227") (name "unconnected-(U1D-TEST_GPIO[18]_3-PadB27)") (class "Default")
      (node (ref "U1") (pin "B27") (pinfunction "TEST_GPIO[18]_3_B27") (pintype "passive+no_connect"))
    )
    (net (code "228") (name "unconnected-(U1D-TEST_GPIO[19]_3-PadD27)") (class "Default")
      (node (ref "U1") (pin "D27") (pinfunction "TEST_GPIO[19]_3_D27") (pintype "passive+no_connect"))
    )
    (net (code "229") (name "unconnected-(U1D-TEST_GPIO[20]_3-PadC27)") (class "Default")
      (node (ref "U1") (pin "C27") (pinfunction "TEST_GPIO[20]_3_C27") (pintype "passive+no_connect"))
    )
    (net (code "230") (name "unconnected-(U1D-TEST_GPIO[21]_3-PadA28)") (class "Default")
      (node (ref "U1") (pin "A28") (pinfunction "TEST_GPIO[21]_3_A28") (pintype "passive+no_connect"))
    )
    (net (code "231") (name "unconnected-(U1D-TEST_GPIO[22]_3-PadB28)") (class "Default")
      (node (ref "U1") (pin "B28") (pinfunction "TEST_GPIO[22]_3_B28") (pintype "passive+no_connect"))
    )
    (net (code "232") (name "unconnected-(U1D-TEST_GPIO[23]_3-PadB29)") (class "Default")
      (node (ref "U1") (pin "B29") (pinfunction "TEST_GPIO[23]_3_B29") (pintype "passive+no_connect"))
    )
    (net (code "233") (name "unconnected-(U1D-TEST_GPIO[24]_3-PadD28)") (class "Default")
      (node (ref "U1") (pin "D28") (pinfunction "TEST_GPIO[24]_3_D28") (pintype "passive+no_connect"))
    )
    (net (code "234") (name "unconnected-(U1D-TEST_GPIO[25]_3-PadC29)") (class "Default")
      (node (ref "U1") (pin "C29") (pinfunction "TEST_GPIO[25]_3_C29") (pintype "passive+no_connect"))
    )
    (net (code "235") (name "unconnected-(U1D-TEST_GPIO[26]_3-PadD29)") (class "Default")
      (node (ref "U1") (pin "D29") (pinfunction "TEST_GPIO[26]_3_D29") (pintype "passive+no_connect"))
    )
    (net (code "236") (name "unconnected-(U1D-TEST_GPIO[27]_3-PadB30)") (class "Default")
      (node (ref "U1") (pin "B30") (pinfunction "TEST_GPIO[27]_3_B30") (pintype "passive+no_connect"))
    )
    (net (code "237") (name "unconnected-(U1D-TEST_GPIO[28]_3-PadA30)") (class "Default")
      (node (ref "U1") (pin "A30") (pinfunction "TEST_GPIO[28]_3_A30") (pintype "passive+no_connect"))
    )
    (net (code "238") (name "unconnected-(U1D-TEST_GPIO[29]_3-PadC30)") (class "Default")
      (node (ref "U1") (pin "C30") (pinfunction "TEST_GPIO[29]_3_C30") (pintype "passive+no_connect"))
    )
    (net (code "239") (name "unconnected-(U1D-TEST_GPIO[30]_3-PadA31)") (class "Default")
      (node (ref "U1") (pin "A31") (pinfunction "TEST_GPIO[30]_3_A31") (pintype "passive+no_connect"))
    )
    (net (code "240") (name "unconnected-(U1D-TEST_GPIO[31]_3-PadA32)") (class "Default")
      (node (ref "U1") (pin "A32") (pinfunction "TEST_GPIO[31]_3_A32") (pintype "passive+no_connect"))
    )
    (net (code "241") (name "unconnected-(U1D-TEST_GPIO[32]_3-PadC31)") (class "Default")
      (node (ref "U1") (pin "C31") (pinfunction "TEST_GPIO[32]_3_C31") (pintype "passive+no_connect"))
    )
    (net (code "242") (name "unconnected-(U1D-TEST_GPIO[33]_3-PadD31)") (class "Default")
      (node (ref "U1") (pin "D31") (pinfunction "TEST_GPIO[33]_3_D31") (pintype "passive+no_connect"))
    )
    (net (code "243") (name "unconnected-(U1D-TEST_GPIO[34]_3-PadD32)") (class "Default")
      (node (ref "U1") (pin "D32") (pinfunction "TEST_GPIO[34]_3_D32") (pintype "passive+no_connect"))
    )
    (net (code "244") (name "unconnected-(U1D-TEST_GPIO[35]_3-PadA33)") (class "Default")
      (node (ref "U1") (pin "A33") (pinfunction "TEST_GPIO[35]_3_A33") (pintype "passive+no_connect"))
    )
    (net (code "245") (name "unconnected-(U1D-TEST_GPIO[36]_3-PadB33)") (class "Default")
      (node (ref "U1") (pin "B33") (pinfunction "TEST_GPIO[36]_3_B33") (pintype "passive+no_connect"))
    )
    (net (code "246") (name "unconnected-(U1D-TEST_GPIO[37]_3-PadD33)") (class "Default")
      (node (ref "U1") (pin "D33") (pinfunction "TEST_GPIO[37]_3_D33") (pintype "passive+no_connect"))
    )
    (net (code "247") (name "unconnected-(U1D-TEST_GPIO[38]_3-PadB34)") (class "Default")
      (node (ref "U1") (pin "B34") (pinfunction "TEST_GPIO[38]_3_B34") (pintype "passive+no_connect"))
    )
    (net (code "248") (name "unconnected-(U1D-TEST_GPIO[39]_3-PadE33)") (class "Default")
      (node (ref "U1") (pin "E33") (pinfunction "TEST_GPIO[39]_3_E33") (pintype "passive+no_connect"))
    )
    (net (code "249") (name "unconnected-(U1D-TEST_GPIO[40]_3-PadC34)") (class "Default")
      (node (ref "U1") (pin "C34") (pinfunction "TEST_GPIO[40]_3_C34") (pintype "passive+no_connect"))
    )
    (net (code "250") (name "unconnected-(U1D-TEST_GPIO[41]_3-PadD34)") (class "Default")
      (node (ref "U1") (pin "D34") (pinfunction "TEST_GPIO[41]_3_D34") (pintype "passive+no_connect"))
    )
    (net (code "251") (name "unconnected-(U1D-TEST_GPIO[42]_3-PadB35)") (class "Default")
      (node (ref "U1") (pin "B35") (pinfunction "TEST_GPIO[42]_3_B35") (pintype "passive+no_connect"))
    )
    (net (code "252") (name "unconnected-(U1D-TEST_GPIO[43]_3-PadF33)") (class "Default")
      (node (ref "U1") (pin "F33") (pinfunction "TEST_GPIO[43]_3_F33") (pintype "passive+no_connect"))
    )
    (net (code "253") (name "unconnected-(U1D-TEST_GPIO[44]_3-PadE34)") (class "Default")
      (node (ref "U1") (pin "E34") (pinfunction "TEST_GPIO[44]_3_E34") (pintype "passive+no_connect"))
    )
    (net (code "254") (name "unconnected-(U1D-TEST_GPIO[45]_3-PadC35)") (class "Default")
      (node (ref "U1") (pin "C35") (pinfunction "TEST_GPIO[45]_3_C35") (pintype "passive+no_connect"))
    )
    (net (code "255") (name "unconnected-(U1D-TEST_GPIO[46]_3-PadC36)") (class "Default")
      (node (ref "U1") (pin "C36") (pinfunction "TEST_GPIO[46]_3_C36") (pintype "passive+no_connect"))
    )
    (net (code "256") (name "unconnected-(U1D-TEST_GPIO[47]_3-PadG33)") (class "Default")
      (node (ref "U1") (pin "G33") (pinfunction "TEST_GPIO[47]_3_G33") (pintype "passive+no_connect"))
    )
    (net (code "257") (name "unconnected-(U1D-TEST_GPIO[48]_3-PadE35)") (class "Default")
      (node (ref "U1") (pin "E35") (pinfunction "TEST_GPIO[48]_3_E35") (pintype "passive+no_connect"))
    )
    (net (code "258") (name "unconnected-(U1D-TEST_GPIO[49]_3-PadD36)") (class "Default")
      (node (ref "U1") (pin "D36") (pinfunction "TEST_GPIO[49]_3_D36") (pintype "passive+no_connect"))
    )
    (net (code "259") (name "unconnected-(U1D-TEST_GPIO[50]_3-PadG34)") (class "Default")
      (node (ref "U1") (pin "G34") (pinfunction "TEST_GPIO[50]_3_G34") (pintype "passive+no_connect"))
    )
    (net (code "260") (name "unconnected-(U1D-TEST_GPIO[51]_3-PadF35)") (class "Default")
      (node (ref "U1") (pin "F35") (pinfunction "TEST_GPIO[51]_3_F35") (pintype "passive+no_connect"))
    )
    (net (code "261") (name "unconnected-(U1D-TEST_GPIO[52]_3-PadN34)") (class "Default")
      (node (ref "U1") (pin "N34") (pinfunction "TEST_GPIO[52]_3_N34") (pintype "passive+no_connect"))
    )
    (net (code "262") (name "unconnected-(U1D-TEST_GPIO[53]_3-PadN35)") (class "Default")
      (node (ref "U1") (pin "N35") (pinfunction "TEST_GPIO[53]_3_N35") (pintype "passive+no_connect"))
    )
    (net (code "263") (name "unconnected-(U1D-TEST_GPIO[54]_3-PadP34)") (class "Default")
      (node (ref "U1") (pin "P34") (pinfunction "TEST_GPIO[54]_3_P34") (pintype "passive+no_connect"))
    )
    (net (code "264") (name "unconnected-(U1D-TEST_GPIO[55]_3-PadP33)") (class "Default")
      (node (ref "U1") (pin "P33") (pinfunction "TEST_GPIO[55]_3_P33") (pintype "passive+no_connect"))
    )
    (net (code "265") (name "unconnected-(U1D-TEST_GPIO[56]_3-PadN36)") (class "Default")
      (node (ref "U1") (pin "N36") (pinfunction "TEST_GPIO[56]_3_N36") (pintype "passive+no_connect"))
    )
    (net (code "266") (name "unconnected-(U1D-TEST_GPIO[57]_3-PadP36)") (class "Default")
      (node (ref "U1") (pin "P36") (pinfunction "TEST_GPIO[57]_3_P36") (pintype "passive+no_connect"))
    )
    (net (code "267") (name "unconnected-(U1D-TEST_GPIO[58]_3-PadR34)") (class "Default")
      (node (ref "U1") (pin "R34") (pinfunction "TEST_GPIO[58]_3_R34") (pintype "passive+no_connect"))
    )
    (net (code "268") (name "unconnected-(U1D-TEST_GPIO[59]_3-PadR33)") (class "Default")
      (node (ref "U1") (pin "R33") (pinfunction "TEST_GPIO[59]_3_R33") (pintype "passive+no_connect"))
    )
    (net (code "269") (name "unconnected-(U1D-TEST_GPIO[60]_3-PadR35)") (class "Default")
      (node (ref "U1") (pin "R35") (pinfunction "TEST_GPIO[60]_3_R35") (pintype "passive+no_connect"))
    )
    (net (code "270") (name "unconnected-(U1D-TEST_GPIO[61]_3-PadT36)") (class "Default")
      (node (ref "U1") (pin "T36") (pinfunction "TEST_GPIO[61]_3_T36") (pintype "passive+no_connect"))
    )
    (net (code "271") (name "unconnected-(U1D-TEST_GPIO[62]_3-PadR36)") (class "Default")
      (node (ref "U1") (pin "R36") (pinfunction "TEST_GPIO[62]_3_R36") (pintype "passive+no_connect"))
    )
    (net (code "272") (name "unconnected-(U1D-TEST_GPIO[63]_3-PadT35)") (class "Default")
      (node (ref "U1") (pin "T35") (pinfunction "TEST_GPIO[63]_3_T35") (pintype "passive+no_connect"))
    )
    (net (code "273") (name "unconnected-(U1D-TEST_GPIO[64]_3-PadT33)") (class "Default")
      (node (ref "U1") (pin "T33") (pinfunction "TEST_GPIO[64]_3_T33") (pintype "passive+no_connect"))
    )
    (net (code "274") (name "unconnected-(U1D-TEST_GPIO[65]_3-PadU34)") (class "Default")
      (node (ref "U1") (pin "U34") (pinfunction "TEST_GPIO[65]_3_U34") (pintype "passive+no_connect"))
    )
    (net (code "275") (name "unconnected-(U1D-TEST_GPIO[66]_3-PadU35)") (class "Default")
      (node (ref "U1") (pin "U35") (pinfunction "TEST_GPIO[66]_3_U35") (pintype "passive+no_connect"))
    )
    (net (code "276") (name "unconnected-(U1D-TEST_GPIO[67]_3-PadU33)") (class "Default")
      (node (ref "U1") (pin "U33") (pinfunction "TEST_GPIO[67]_3_U33") (pintype "passive+no_connect"))
    )
    (net (code "277") (name "unconnected-(U1D-TEST_GPIO[68]_3-PadV36)") (class "Default")
      (node (ref "U1") (pin "V36") (pinfunction "TEST_GPIO[68]_3_V36") (pintype "passive+no_connect"))
    )
    (net (code "278") (name "unconnected-(U1D-TEST_GPIO[69]_3-PadV34)") (class "Default")
      (node (ref "U1") (pin "V34") (pinfunction "TEST_GPIO[69]_3_V34") (pintype "passive+no_connect"))
    )
    (net (code "279") (name "unconnected-(U1D-TEST_GPIO[70]_3-PadV35)") (class "Default")
      (node (ref "U1") (pin "V35") (pinfunction "TEST_GPIO[70]_3_V35") (pintype "passive+no_connect"))
    )
    (net (code "280") (name "unconnected-(U1D-TEST_GPIO[71]_3-PadV32)") (class "Default")
      (node (ref "U1") (pin "V32") (pinfunction "TEST_GPIO[71]_3_V32") (pintype "passive+no_connect"))
    )
    (net (code "281") (name "unconnected-(U1E-DBG_SPARE[0]_4-PadC12)") (class "Default")
      (node (ref "U1") (pin "C12") (pinfunction "DBG_SPARE[0]_4_C12") (pintype "passive+no_connect"))
    )
    (net (code "282") (name "unconnected-(U1E-DBG_SPARE[1]_4-PadB12)") (class "Default")
      (node (ref "U1") (pin "B12") (pinfunction "DBG_SPARE[1]_4_B12") (pintype "passive+no_connect"))
    )
    (net (code "283") (name "unconnected-(U1E-JTG_TCK_4-PadL4)") (class "Default")
      (node (ref "U1") (pin "L4") (pinfunction "JTG_TCK_4_L4") (pintype "passive+no_connect"))
    )
    (net (code "284") (name "unconnected-(U1E-JTG_TDI_4-PadL1)") (class "Default")
      (node (ref "U1") (pin "L1") (pinfunction "JTG_TDI_4_L1") (pintype "passive+no_connect"))
    )
    (net (code "285") (name "unconnected-(U1E-JTG_TDO_4-PadM3)") (class "Default")
      (node (ref "U1") (pin "M3") (pinfunction "JTG_TDO_4_M3") (pintype "passive+no_connect"))
    )
    (net (code "286") (name "unconnected-(U1E-JTG_TMS_4-PadM1)") (class "Default")
      (node (ref "U1") (pin "M1") (pinfunction "JTG_TMS_4_M1") (pintype "passive+no_connect"))
    )
    (net (code "287") (name "unconnected-(U1E-TEST_GPIO[0]_4-PadV2)") (class "Default")
      (node (ref "U1") (pin "V2") (pinfunction "TEST_GPIO[0]_4_V2") (pintype "passive+no_connect"))
    )
    (net (code "288") (name "unconnected-(U1E-TEST_GPIO[1]_4-PadU2)") (class "Default")
      (node (ref "U1") (pin "U2") (pinfunction "TEST_GPIO[1]_4_U2") (pintype "passive+no_connect"))
    )
    (net (code "289") (name "unconnected-(U1E-TEST_GPIO[2]_4-PadU3)") (class "Default")
      (node (ref "U1") (pin "U3") (pinfunction "TEST_GPIO[2]_4_U3") (pintype "passive+no_connect"))
    )
    (net (code "290") (name "unconnected-(U1E-TEST_GPIO[3]_4-PadU1)") (class "Default")
      (node (ref "U1") (pin "U1") (pinfunction "TEST_GPIO[3]_4_U1") (pintype "passive+no_connect"))
    )
    (net (code "291") (name "unconnected-(U1E-TEST_GPIO[4]_4-PadT4)") (class "Default")
      (node (ref "U1") (pin "T4") (pinfunction "TEST_GPIO[4]_4_T4") (pintype "passive+no_connect"))
    )
    (net (code "292") (name "unconnected-(U1E-TEST_GPIO[5]_4-PadT1)") (class "Default")
      (node (ref "U1") (pin "T1") (pinfunction "TEST_GPIO[5]_4_T1") (pintype "passive+no_connect"))
    )
    (net (code "293") (name "unconnected-(U1E-TEST_GPIO[6]_4-PadT3)") (class "Default")
      (node (ref "U1") (pin "T3") (pinfunction "TEST_GPIO[6]_4_T3") (pintype "passive+no_connect"))
    )
    (net (code "294") (name "unconnected-(U1E-TEST_GPIO[7]_4-PadR4)") (class "Default")
      (node (ref "U1") (pin "R4") (pinfunction "TEST_GPIO[7]_4_R4") (pintype "passive+no_connect"))
    )
    (net (code "295") (name "unconnected-(U1E-TEST_GPIO[8]_4-PadR3)") (class "Default")
      (node (ref "U1") (pin "R3") (pinfunction "TEST_GPIO[8]_4_R3") (pintype "passive+no_connect"))
    )
    (net (code "296") (name "unconnected-(U1E-TEST_GPIO[9]_4-PadR1)") (class "Default")
      (node (ref "U1") (pin "R1") (pinfunction "TEST_GPIO[9]_4_R1") (pintype "passive+no_connect"))
    )
    (net (code "297") (name "unconnected-(U1E-TEST_GPIO[10]_4-PadR2)") (class "Default")
      (node (ref "U1") (pin "R2") (pinfunction "TEST_GPIO[10]_4_R2") (pintype "passive+no_connect"))
    )
    (net (code "298") (name "unconnected-(U1E-TEST_GPIO[11]_4-PadP4)") (class "Default")
      (node (ref "U1") (pin "P4") (pinfunction "TEST_GPIO[11]_4_P4") (pintype "passive+no_connect"))
    )
    (net (code "299") (name "unconnected-(U1E-TEST_GPIO[12]_4-PadP2)") (class "Default")
      (node (ref "U1") (pin "P2") (pinfunction "TEST_GPIO[12]_4_P2") (pintype "passive+no_connect"))
    )
    (net (code "300") (name "unconnected-(U1E-TEST_GPIO[13]_4-PadN2)") (class "Default")
      (node (ref "U1") (pin "N2") (pinfunction "TEST_GPIO[13]_4_N2") (pintype "passive+no_connect"))
    )
    (net (code "301") (name "unconnected-(U1E-TEST_GPIO[14]_4-PadP1)") (class "Default")
      (node (ref "U1") (pin "P1") (pinfunction "TEST_GPIO[14]_4_P1") (pintype "passive+no_connect"))
    )
    (net (code "302") (name "unconnected-(U1E-TEST_GPIO[15]_4-PadN3)") (class "Default")
      (node (ref "U1") (pin "N3") (pinfunction "TEST_GPIO[15]_4_N3") (pintype "passive+no_connect"))
    )
    (net (code "303") (name "unconnected-(U1E-TEST_GPIO[16]_4-PadL3)") (class "Default")
      (node (ref "U1") (pin "L3") (pinfunction "TEST_GPIO[16]_4_L3") (pintype "passive+no_connect"))
    )
    (net (code "304") (name "unconnected-(U1E-TEST_GPIO[17]_4-PadK1)") (class "Default")
      (node (ref "U1") (pin "K1") (pinfunction "TEST_GPIO[17]_4_K1") (pintype "passive+no_connect"))
    )
    (net (code "305") (name "unconnected-(U1E-TEST_GPIO[18]_4-PadK2)") (class "Default")
      (node (ref "U1") (pin "K2") (pinfunction "TEST_GPIO[18]_4_K2") (pintype "passive+no_connect"))
    )
    (net (code "306") (name "unconnected-(U1E-TEST_GPIO[19]_4-PadK4)") (class "Default")
      (node (ref "U1") (pin "K4") (pinfunction "TEST_GPIO[19]_4_K4") (pintype "passive+no_connect"))
    )
    (net (code "307") (name "unconnected-(U1E-TEST_GPIO[20]_4-PadK3)") (class "Default")
      (node (ref "U1") (pin "K3") (pinfunction "TEST_GPIO[20]_4_K3") (pintype "passive+no_connect"))
    )
    (net (code "308") (name "unconnected-(U1E-TEST_GPIO[21]_4-PadJ1)") (class "Default")
      (node (ref "U1") (pin "J1") (pinfunction "TEST_GPIO[21]_4_J1") (pintype "passive+no_connect"))
    )
    (net (code "309") (name "unconnected-(U1E-TEST_GPIO[22]_4-PadJ2)") (class "Default")
      (node (ref "U1") (pin "J2") (pinfunction "TEST_GPIO[22]_4_J2") (pintype "passive+no_connect"))
    )
    (net (code "310") (name "unconnected-(U1E-TEST_GPIO[23]_4-PadH2)") (class "Default")
      (node (ref "U1") (pin "H2") (pinfunction "TEST_GPIO[23]_4_H2") (pintype "passive+no_connect"))
    )
    (net (code "311") (name "unconnected-(U1E-TEST_GPIO[24]_4-PadJ4)") (class "Default")
      (node (ref "U1") (pin "J4") (pinfunction "TEST_GPIO[24]_4_J4") (pintype "passive+no_connect"))
    )
    (net (code "312") (name "unconnected-(U1E-TEST_GPIO[25]_4-PadH3)") (class "Default")
      (node (ref "U1") (pin "H3") (pinfunction "TEST_GPIO[25]_4_H3") (pintype "passive+no_connect"))
    )
    (net (code "313") (name "unconnected-(U1E-TEST_GPIO[26]_4-PadH4)") (class "Default")
      (node (ref "U1") (pin "H4") (pinfunction "TEST_GPIO[26]_4_H4") (pintype "passive+no_connect"))
    )
    (net (code "314") (name "unconnected-(U1E-TEST_GPIO[27]_4-PadG2)") (class "Default")
      (node (ref "U1") (pin "G2") (pinfunction "TEST_GPIO[27]_4_G2") (pintype "passive+no_connect"))
    )
    (net (code "315") (name "unconnected-(U1E-TEST_GPIO[28]_4-PadG1)") (class "Default")
      (node (ref "U1") (pin "G1") (pinfunction "TEST_GPIO[28]_4_G1") (pintype "passive+no_connect"))
    )
    (net (code "316") (name "unconnected-(U1E-TEST_GPIO[29]_4-PadG3)") (class "Default")
      (node (ref "U1") (pin "G3") (pinfunction "TEST_GPIO[29]_4_G3") (pintype "passive+no_connect"))
    )
    (net (code "317") (name "unconnected-(U1E-TEST_GPIO[30]_4-PadF1)") (class "Default")
      (node (ref "U1") (pin "F1") (pinfunction "TEST_GPIO[30]_4_F1") (pintype "passive+no_connect"))
    )
    (net (code "318") (name "unconnected-(U1E-TEST_GPIO[31]_4-PadE1)") (class "Default")
      (node (ref "U1") (pin "E1") (pinfunction "TEST_GPIO[31]_4_E1") (pintype "passive+no_connect"))
    )
    (net (code "319") (name "unconnected-(U1E-TEST_GPIO[32]_4-PadF3)") (class "Default")
      (node (ref "U1") (pin "F3") (pinfunction "TEST_GPIO[32]_4_F3") (pintype "passive+no_connect"))
    )
    (net (code "320") (name "unconnected-(U1E-TEST_GPIO[33]_4-PadF4)") (class "Default")
      (node (ref "U1") (pin "F4") (pinfunction "TEST_GPIO[33]_4_F4") (pintype "passive+no_connect"))
    )
    (net (code "321") (name "unconnected-(U1E-TEST_GPIO[34]_4-PadE4)") (class "Default")
      (node (ref "U1") (pin "E4") (pinfunction "TEST_GPIO[34]_4_E4") (pintype "passive+no_connect"))
    )
    (net (code "322") (name "unconnected-(U1E-TEST_GPIO[35]_4-PadD1)") (class "Default")
      (node (ref "U1") (pin "D1") (pinfunction "TEST_GPIO[35]_4_D1") (pintype "passive+no_connect"))
    )
    (net (code "323") (name "unconnected-(U1E-TEST_GPIO[36]_4-PadD2)") (class "Default")
      (node (ref "U1") (pin "D2") (pinfunction "TEST_GPIO[36]_4_D2") (pintype "passive+no_connect"))
    )
    (net (code "324") (name "unconnected-(U1E-TEST_GPIO[37]_4-PadD4)") (class "Default")
      (node (ref "U1") (pin "D4") (pinfunction "TEST_GPIO[37]_4_D4") (pintype "passive+no_connect"))
    )
    (net (code "325") (name "unconnected-(U1E-TEST_GPIO[38]_4-PadC2)") (class "Default")
      (node (ref "U1") (pin "C2") (pinfunction "TEST_GPIO[38]_4_C2") (pintype "passive+no_connect"))
    )
    (net (code "326") (name "unconnected-(U1E-TEST_GPIO[39]_4-PadD5)") (class "Default")
      (node (ref "U1") (pin "D5") (pinfunction "TEST_GPIO[39]_4_D5") (pintype "passive+no_connect"))
    )
    (net (code "327") (name "unconnected-(U1E-TEST_GPIO[40]_4-PadC3)") (class "Default")
      (node (ref "U1") (pin "C3") (pinfunction "TEST_GPIO[40]_4_C3") (pintype "passive+no_connect"))
    )
    (net (code "328") (name "unconnected-(U1E-TEST_GPIO[41]_4-PadC4)") (class "Default")
      (node (ref "U1") (pin "C4") (pinfunction "TEST_GPIO[41]_4_C4") (pintype "passive+no_connect"))
    )
    (net (code "329") (name "unconnected-(U1E-TEST_GPIO[42]_4-PadB2)") (class "Default")
      (node (ref "U1") (pin "B2") (pinfunction "TEST_GPIO[42]_4_B2") (pintype "passive+no_connect"))
    )
    (net (code "330") (name "unconnected-(U1E-TEST_GPIO[43]_4-PadD6)") (class "Default")
      (node (ref "U1") (pin "D6") (pinfunction "TEST_GPIO[43]_4_D6") (pintype "passive+no_connect"))
    )
    (net (code "331") (name "unconnected-(U1E-TEST_GPIO[44]_4-PadC5)") (class "Default")
      (node (ref "U1") (pin "C5") (pinfunction "TEST_GPIO[44]_4_C5") (pintype "passive+no_connect"))
    )
    (net (code "332") (name "unconnected-(U1E-TEST_GPIO[45]_4-PadB3)") (class "Default")
      (node (ref "U1") (pin "B3") (pinfunction "TEST_GPIO[45]_4_B3") (pintype "passive+no_connect"))
    )
    (net (code "333") (name "unconnected-(U1E-TEST_GPIO[46]_4-PadA3)") (class "Default")
      (node (ref "U1") (pin "A3") (pinfunction "TEST_GPIO[46]_4_A3") (pintype "passive+no_connect"))
    )
    (net (code "334") (name "unconnected-(U1E-TEST_GPIO[47]_4-PadD7)") (class "Default")
      (node (ref "U1") (pin "D7") (pinfunction "TEST_GPIO[47]_4_D7") (pintype "passive+no_connect"))
    )
    (net (code "335") (name "unconnected-(U1E-TEST_GPIO[48]_4-PadB5)") (class "Default")
      (node (ref "U1") (pin "B5") (pinfunction "TEST_GPIO[48]_4_B5") (pintype "passive+no_connect"))
    )
    (net (code "336") (name "unconnected-(U1E-TEST_GPIO[49]_4-PadA4)") (class "Default")
      (node (ref "U1") (pin "A4") (pinfunction "TEST_GPIO[49]_4_A4") (pintype "passive+no_connect"))
    )
    (net (code "337") (name "unconnected-(U1E-TEST_GPIO[50]_4-PadC7)") (class "Default")
      (node (ref "U1") (pin "C7") (pinfunction "TEST_GPIO[50]_4_C7") (pintype "passive+no_connect"))
    )
    (net (code "338") (name "unconnected-(U1E-TEST_GPIO[51]_4-PadB6)") (class "Default")
      (node (ref "U1") (pin "B6") (pinfunction "TEST_GPIO[51]_4_B6") (pintype "passive+no_connect"))
    )
    (net (code "339") (name "unconnected-(U1E-TEST_GPIO[52]_4-PadC13)") (class "Default")
      (node (ref "U1") (pin "C13") (pinfunction "TEST_GPIO[52]_4_C13") (pintype "passive+no_connect"))
    )
    (net (code "340") (name "unconnected-(U1E-TEST_GPIO[53]_4-PadB13)") (class "Default")
      (node (ref "U1") (pin "B13") (pinfunction "TEST_GPIO[53]_4_B13") (pintype "passive+no_connect"))
    )
    (net (code "341") (name "unconnected-(U1E-TEST_GPIO[54]_4-PadC14)") (class "Default")
      (node (ref "U1") (pin "C14") (pinfunction "TEST_GPIO[54]_4_C14") (pintype "passive+no_connect"))
    )
    (net (code "342") (name "unconnected-(U1E-TEST_GPIO[55]_4-PadD14)") (class "Default")
      (node (ref "U1") (pin "D14") (pinfunction "TEST_GPIO[55]_4_D14") (pintype "passive+no_connect"))
    )
    (net (code "343") (name "unconnected-(U1E-TEST_GPIO[56]_4-PadA13)") (class "Default")
      (node (ref "U1") (pin "A13") (pinfunction "TEST_GPIO[56]_4_A13") (pintype "passive+no_connect"))
    )
    (net (code "344") (name "unconnected-(U1E-TEST_GPIO[57]_4-PadA14)") (class "Default")
      (node (ref "U1") (pin "A14") (pinfunction "TEST_GPIO[57]_4_A14") (pintype "passive+no_connect"))
    )
    (net (code "345") (name "unconnected-(U1E-TEST_GPIO[58]_4-PadC15)") (class "Default")
      (node (ref "U1") (pin "C15") (pinfunction "TEST_GPIO[58]_4_C15") (pintype "passive+no_connect"))
    )
    (net (code "346") (name "unconnected-(U1E-TEST_GPIO[59]_4-PadD15)") (class "Default")
      (node (ref "U1") (pin "D15") (pinfunction "TEST_GPIO[59]_4_D15") (pintype "passive+no_connect"))
    )
    (net (code "347") (name "unconnected-(U1E-TEST_GPIO[60]_4-PadB15)") (class "Default")
      (node (ref "U1") (pin "B15") (pinfunction "TEST_GPIO[60]_4_B15") (pintype "passive+no_connect"))
    )
    (net (code "348") (name "unconnected-(U1E-TEST_GPIO[61]_4-PadA16)") (class "Default")
      (node (ref "U1") (pin "A16") (pinfunction "TEST_GPIO[61]_4_A16") (pintype "passive+no_connect"))
    )
    (net (code "349") (name "unconnected-(U1E-TEST_GPIO[62]_4-PadA15)") (class "Default")
      (node (ref "U1") (pin "A15") (pinfunction "TEST_GPIO[62]_4_A15") (pintype "passive+no_connect"))
    )
    (net (code "350") (name "unconnected-(U1E-TEST_GPIO[63]_4-PadB16)") (class "Default")
      (node (ref "U1") (pin "B16") (pinfunction "TEST_GPIO[63]_4_B16") (pintype "passive+no_connect"))
    )
    (net (code "351") (name "unconnected-(U1E-TEST_GPIO[64]_4-PadD16)") (class "Default")
      (node (ref "U1") (pin "D16") (pinfunction "TEST_GPIO[64]_4_D16") (pintype "passive+no_connect"))
    )
    (net (code "352") (name "unconnected-(U1E-TEST_GPIO[65]_4-PadC17)") (class "Default")
      (node (ref "U1") (pin "C17") (pinfunction "TEST_GPIO[65]_4_C17") (pintype "passive+no_connect"))
    )
    (net (code "353") (name "unconnected-(U1E-TEST_GPIO[66]_4-PadB17)") (class "Default")
      (node (ref "U1") (pin "B17") (pinfunction "TEST_GPIO[66]_4_B17") (pintype "passive+no_connect"))
    )
    (net (code "354") (name "unconnected-(U1E-TEST_GPIO[67]_4-PadD17)") (class "Default")
      (node (ref "U1") (pin "D17") (pinfunction "TEST_GPIO[67]_4_D17") (pintype "passive+no_connect"))
    )
    (net (code "355") (name "unconnected-(U1E-TEST_GPIO[68]_4-PadA18)") (class "Default")
      (node (ref "U1") (pin "A18") (pinfunction "TEST_GPIO[68]_4_A18") (pintype "passive+no_connect"))
    )
    (net (code "356") (name "unconnected-(U1E-TEST_GPIO[69]_4-PadC18)") (class "Default")
      (node (ref "U1") (pin "C18") (pinfunction "TEST_GPIO[69]_4_C18") (pintype "passive+no_connect"))
    )
    (net (code "357") (name "unconnected-(U1E-TEST_GPIO[70]_4-PadB18)") (class "Default")
      (node (ref "U1") (pin "B18") (pinfunction "TEST_GPIO[70]_4_B18") (pintype "passive+no_connect"))
    )
    (net (code "358") (name "unconnected-(U1E-TEST_GPIO[71]_4-PadE18)") (class "Default")
      (node (ref "U1") (pin "E18") (pinfunction "TEST_GPIO[71]_4_E18") (pintype "passive+no_connect"))
    )
  )
)
